# ACB-Light-R1_0-J04.net
KiCad netlist of a schematic drawn in EAGLE
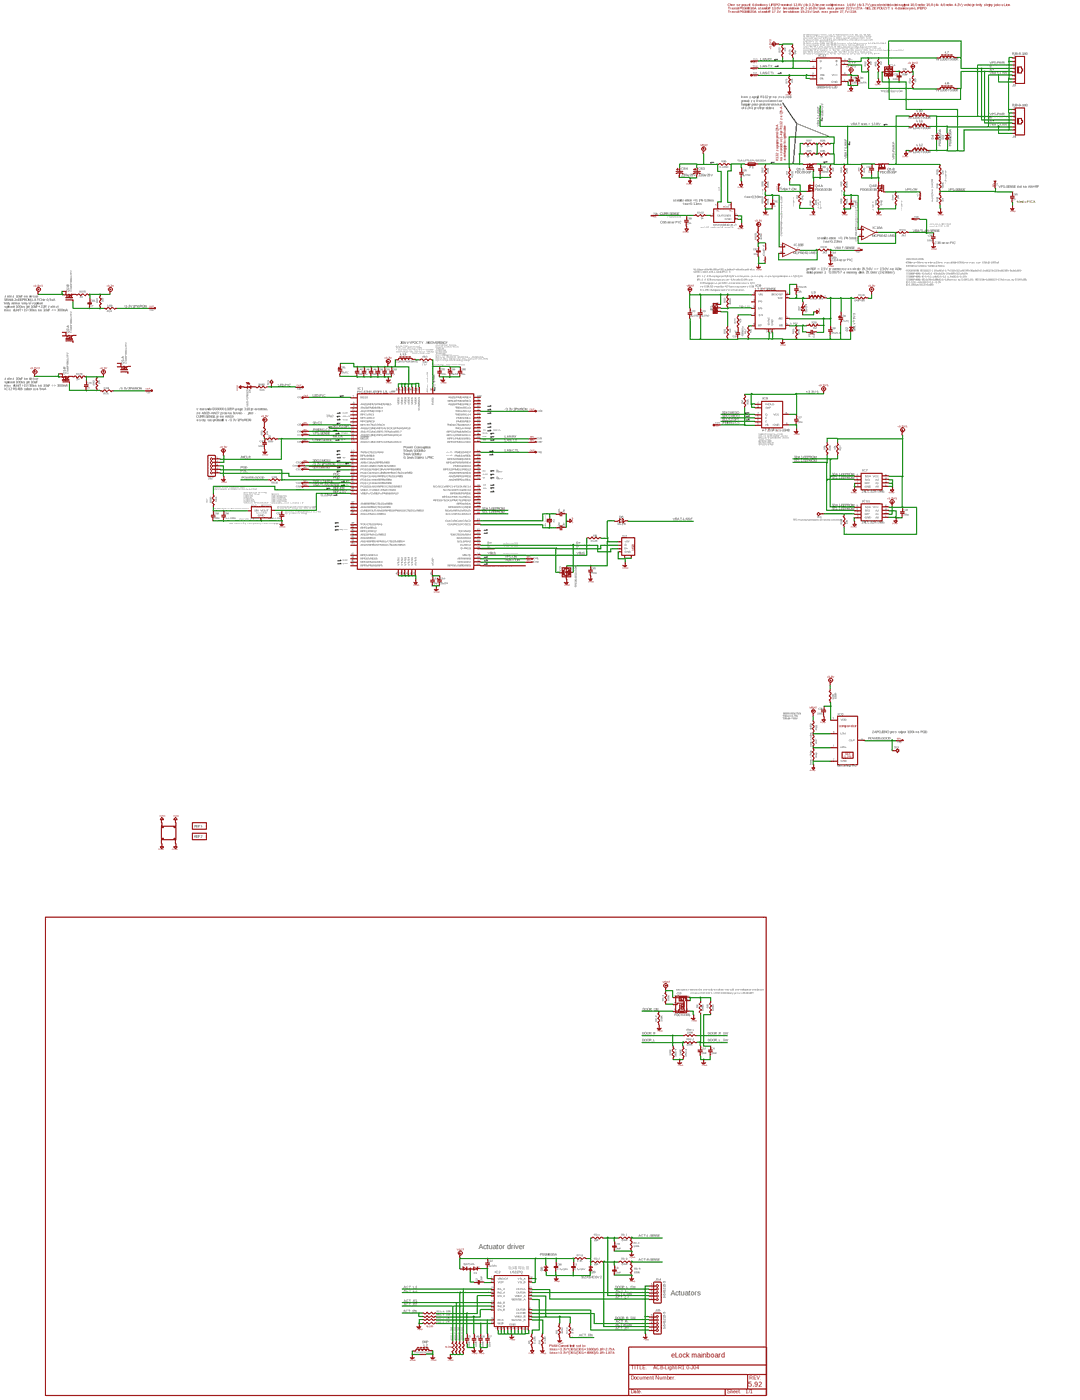
[diagram p0: schematic, sheet 1, overview]
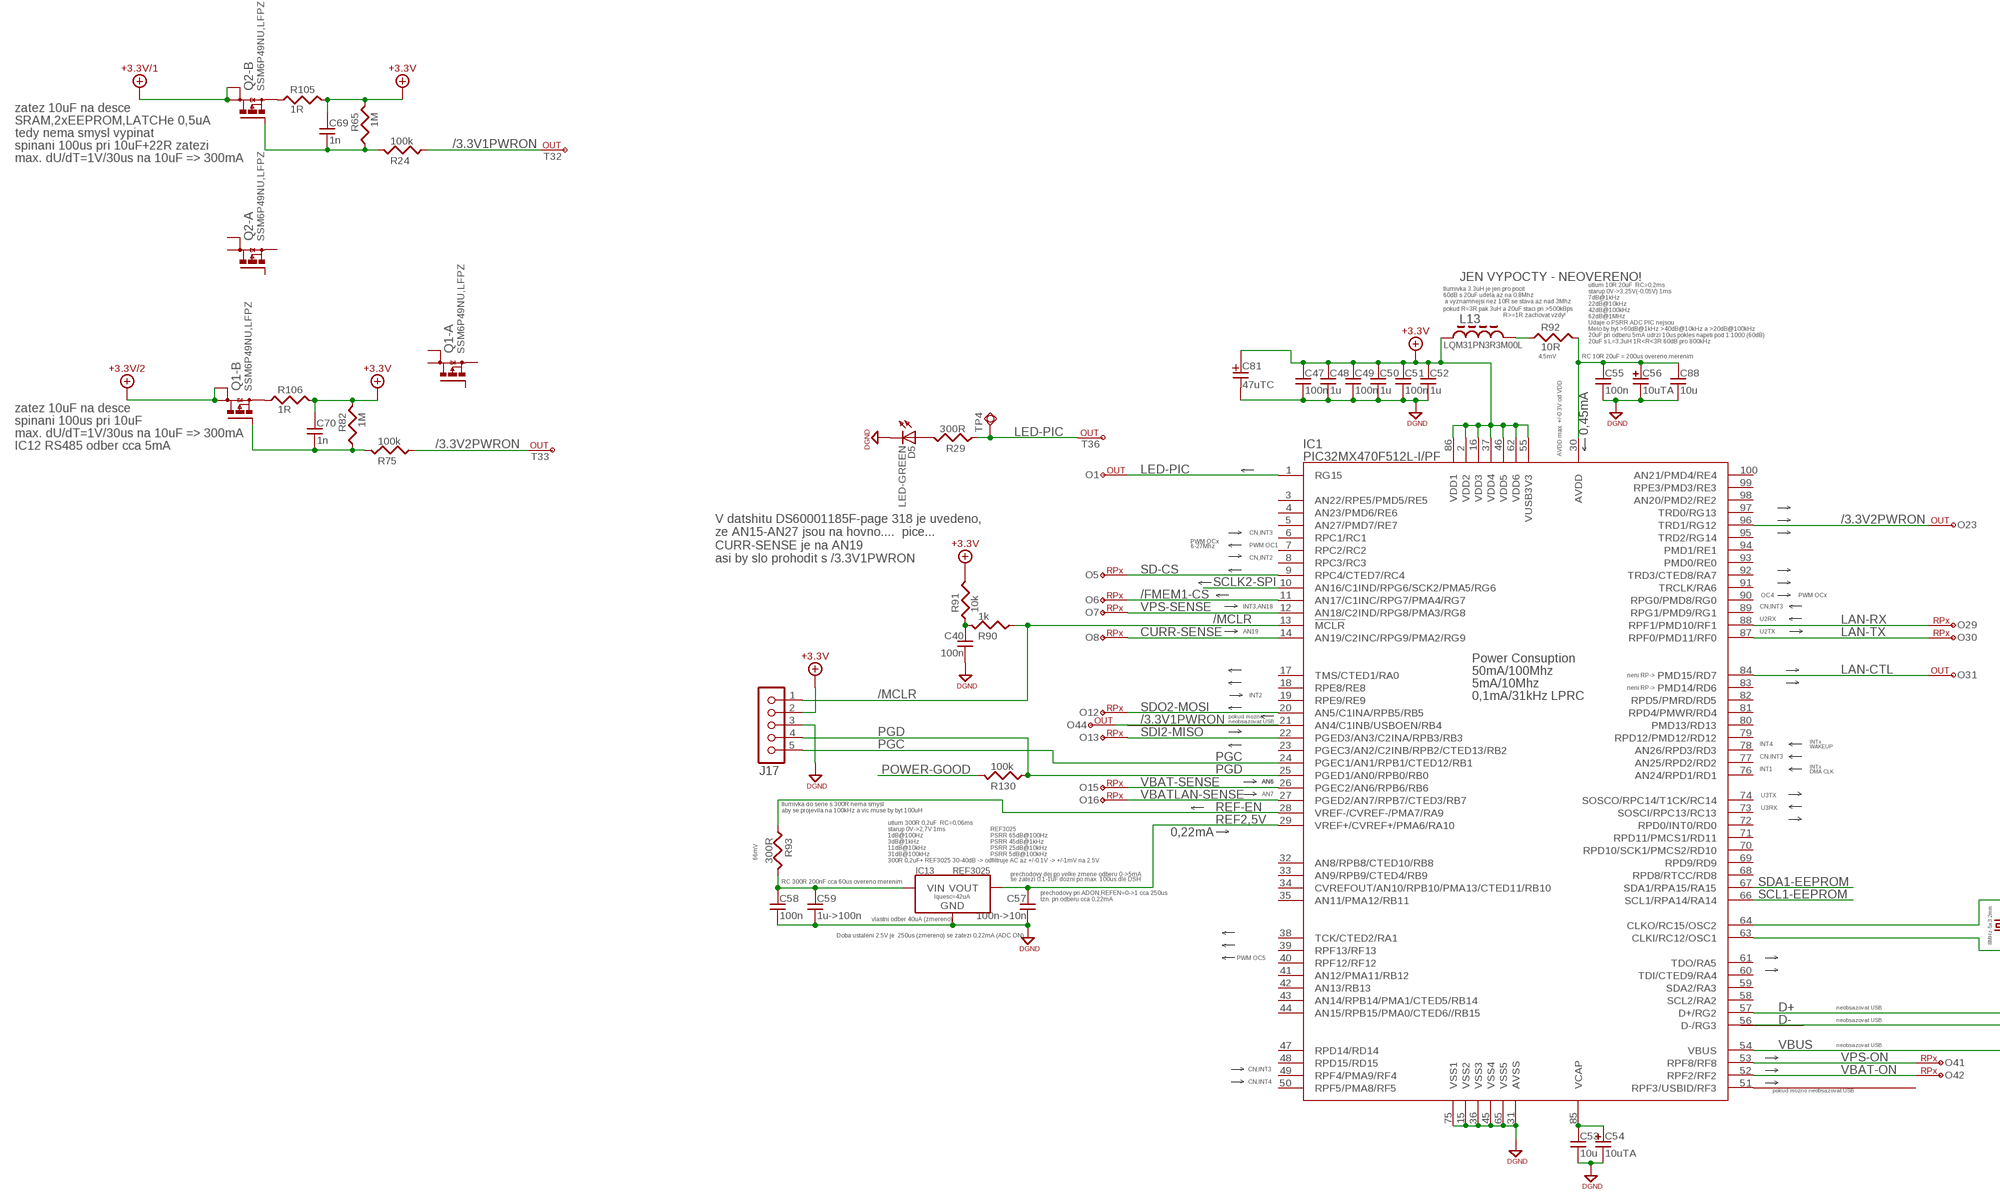
[diagram p1: schematic, sheet 1, part 1 of 5]
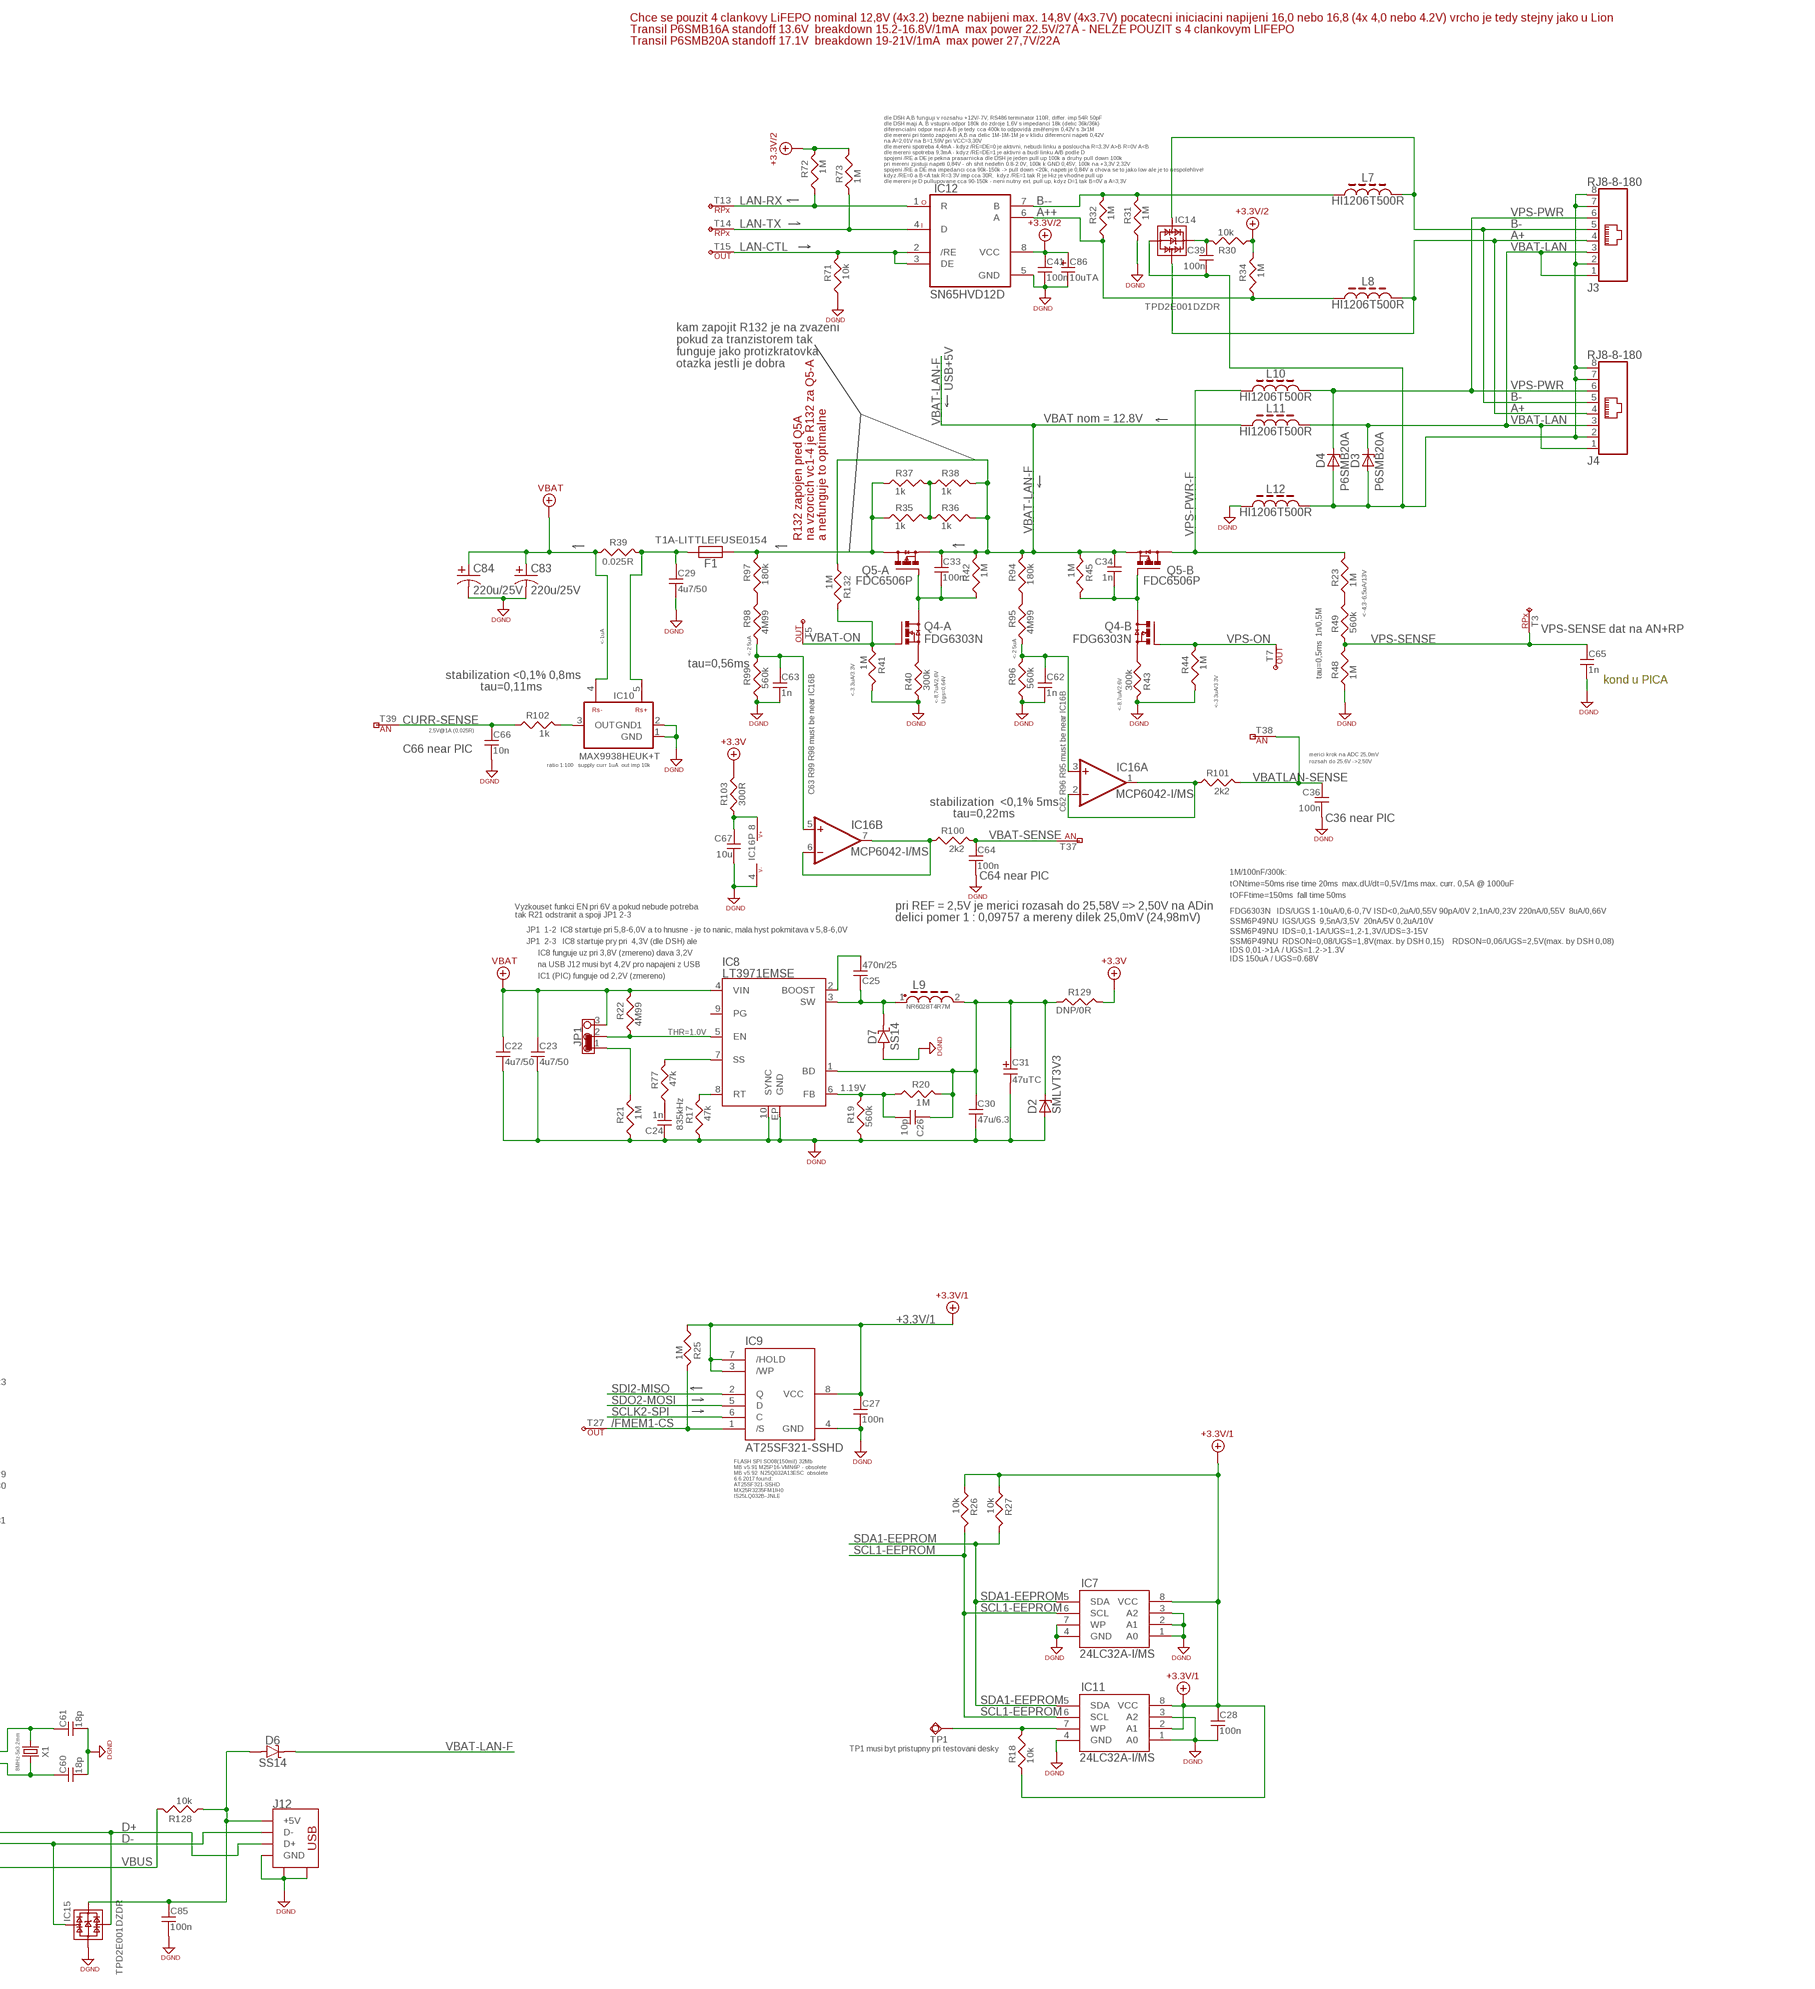
[diagram p2: schematic, sheet 1, part 2 of 5]
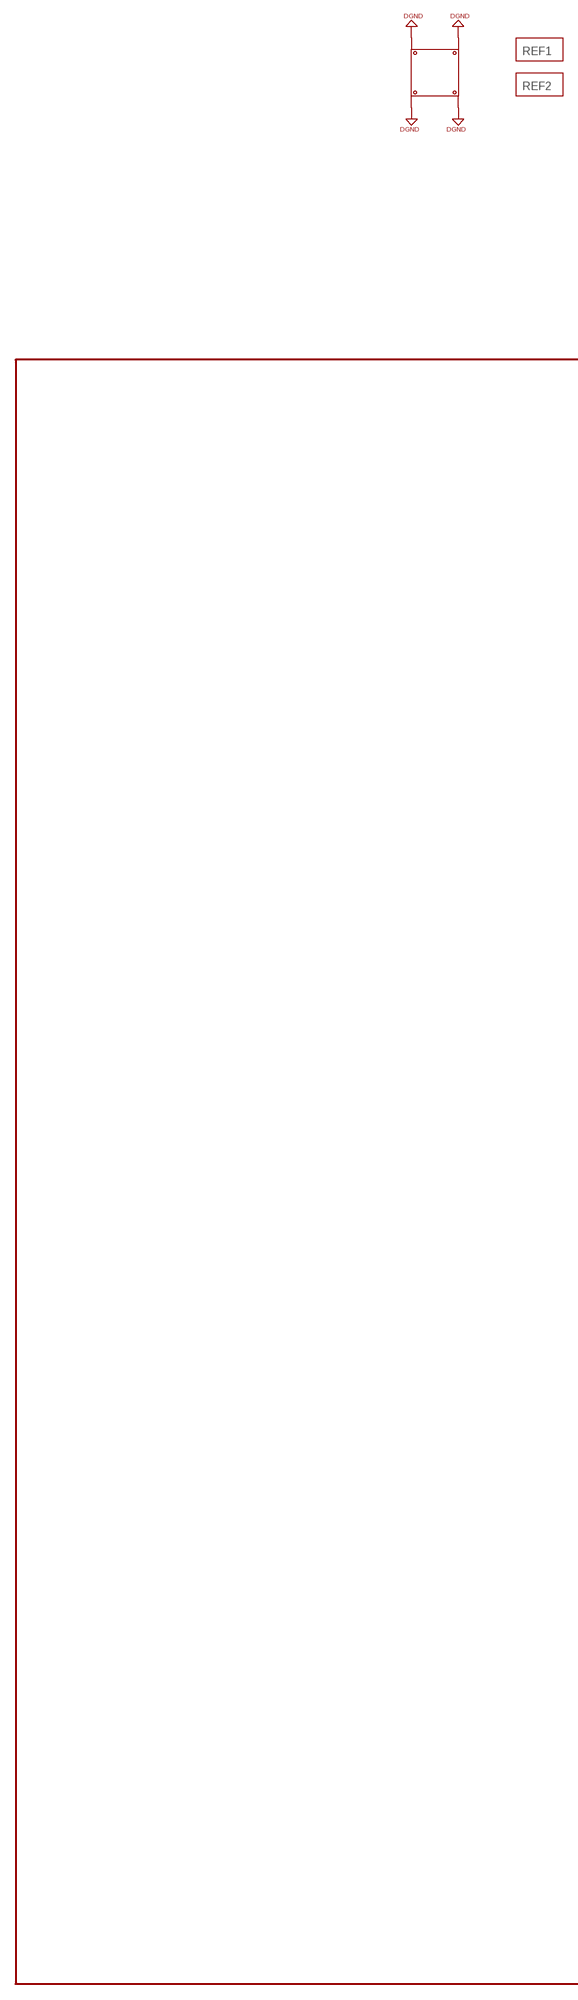
[diagram p3: schematic, sheet 1, part 3 of 5]
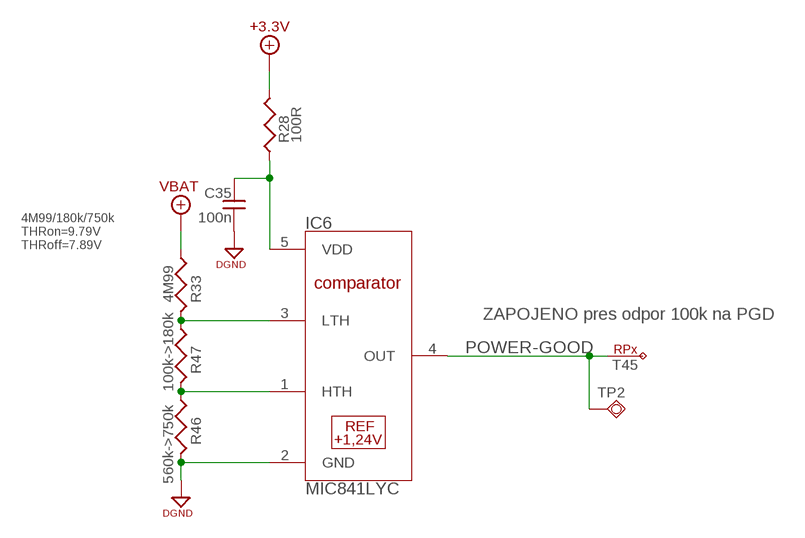
[diagram p4: schematic, sheet 1, part 4 of 5]
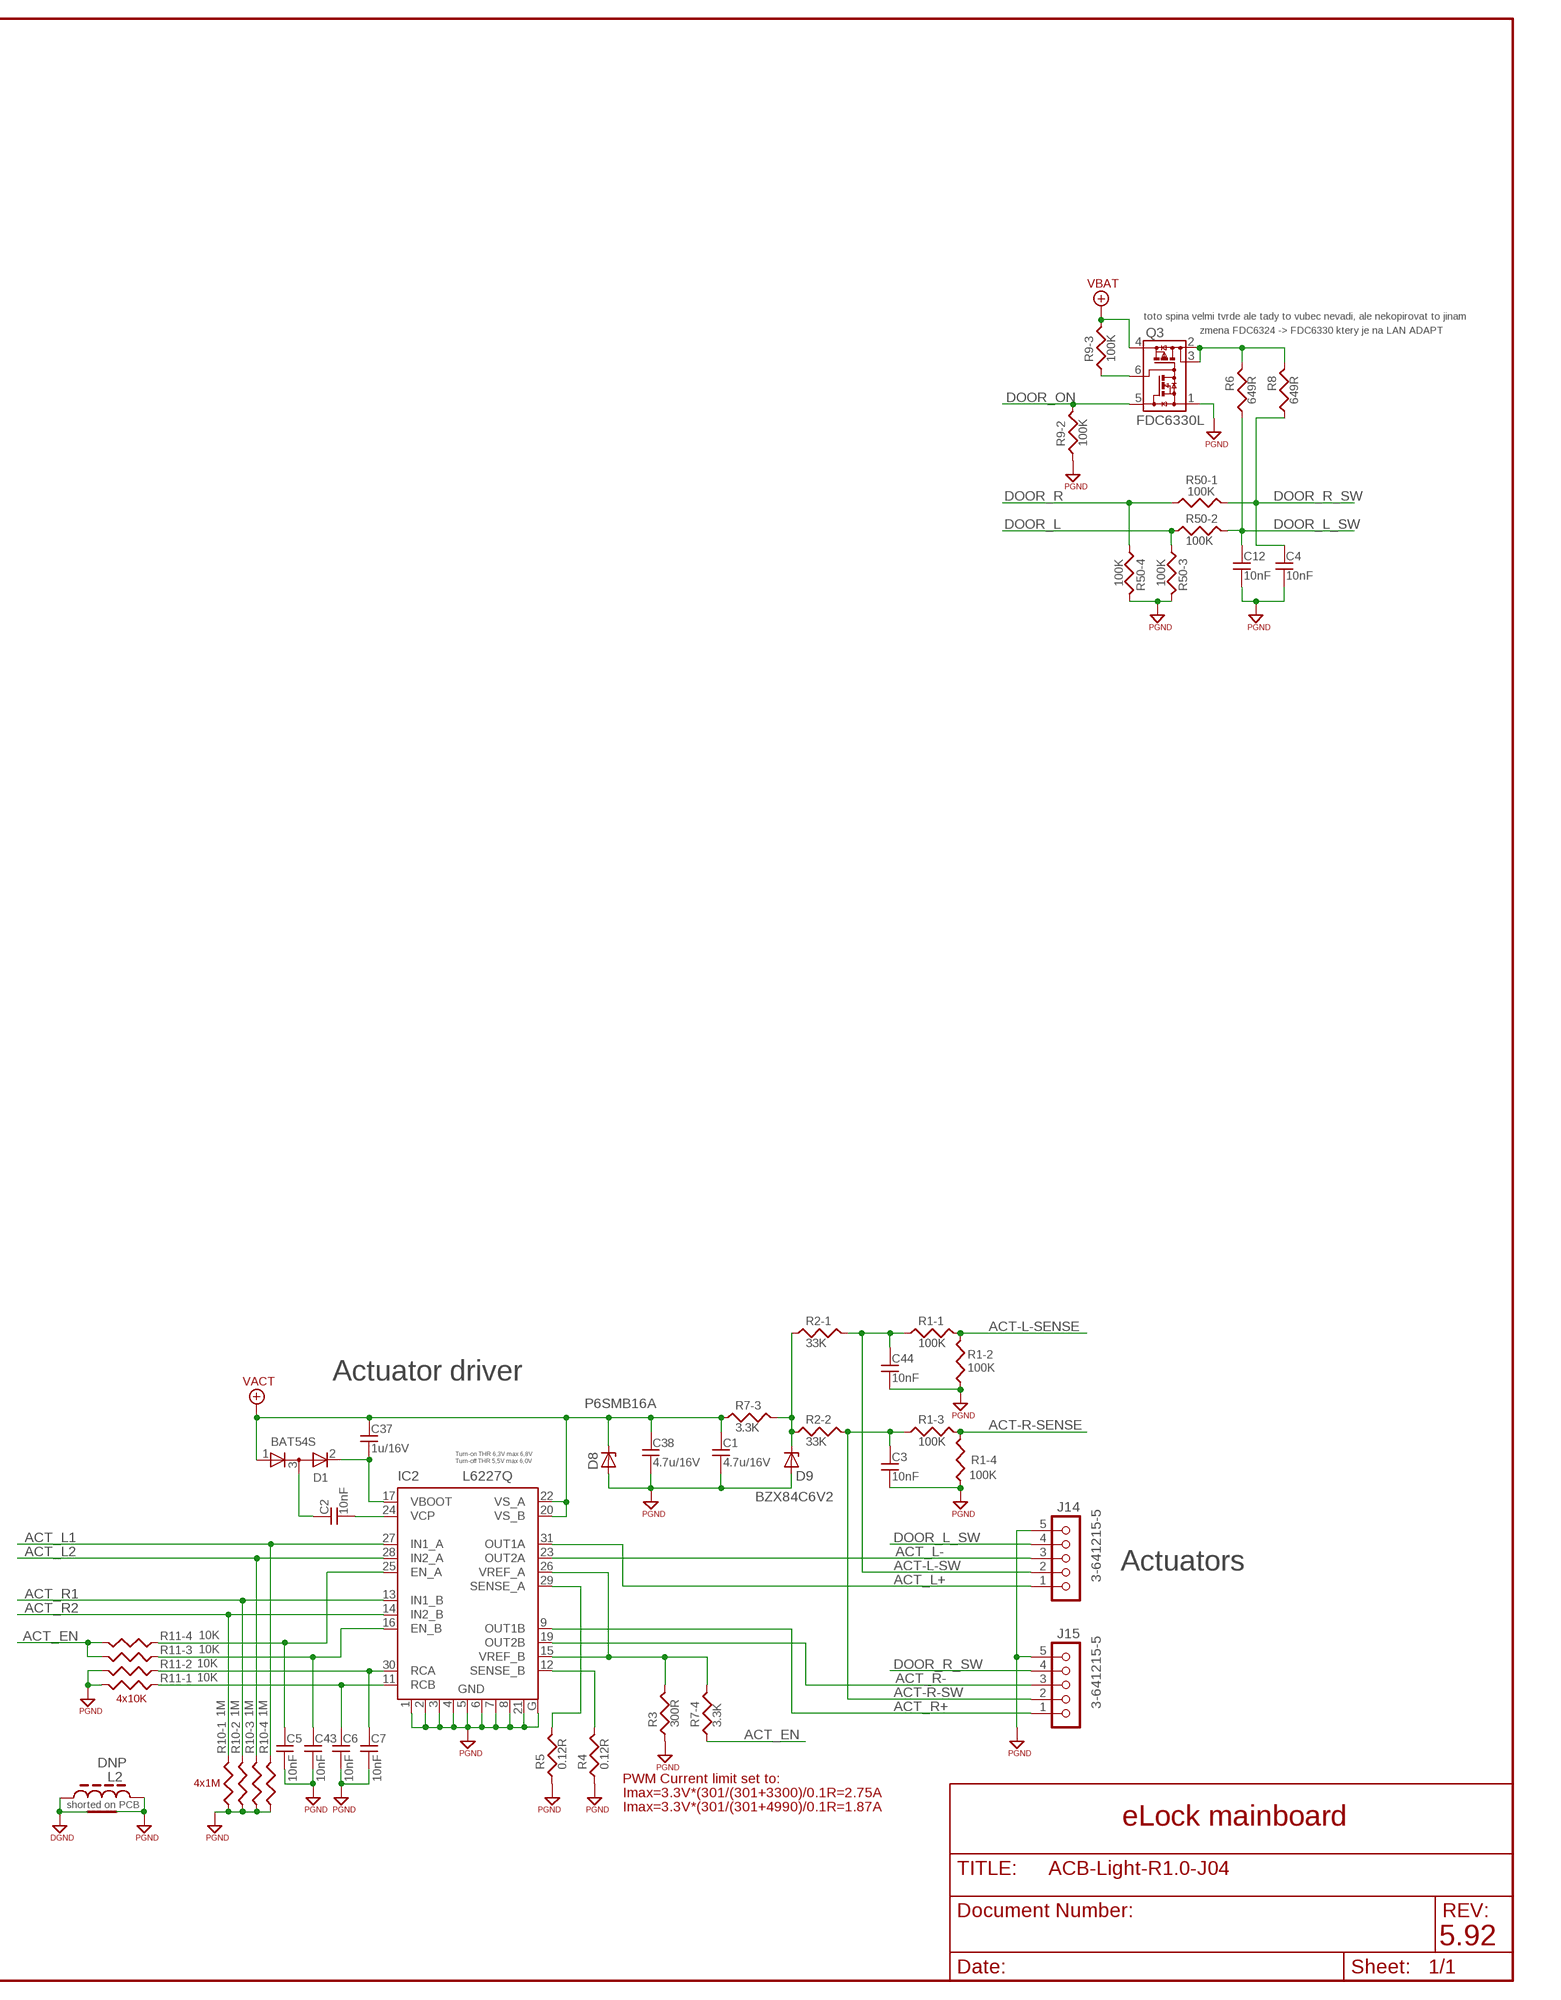
[diagram p5: schematic, sheet 1, part 5 of 5]

(export (version "E")
  (design (tool "Eeschema 10.0.6"))
  (components
    (comp (ref "C1")
      (value "4.7u/16V")
      (footprint "eagle-import:0805")
      (libsource (lib "eagle-import") (part "C-0805"))
    )
    (comp (ref "C2")
      (value "10nF")
      (footprint "eagle-import:0603")
      (libsource (lib "eagle-import") (part "C-0603"))
    )
    (comp (ref "C3")
      (value "10nF")
      (footprint "eagle-import:0603")
      (libsource (lib "eagle-import") (part "C-0603"))
    )
    (comp (ref "C4")
      (value "10nF")
      (footprint "eagle-import:0603")
      (libsource (lib "eagle-import") (part "C-0603"))
    )
    (comp (ref "C5")
      (value "10nF")
      (footprint "eagle-import:0603")
      (libsource (lib "eagle-import") (part "C-0603"))
    )
    (comp (ref "C6")
      (value "10nF")
      (footprint "eagle-import:0603")
      (libsource (lib "eagle-import") (part "C-0603"))
    )
    (comp (ref "C7")
      (value "10nF")
      (footprint "eagle-import:0603")
      (libsource (lib "eagle-import") (part "C-0603"))
    )
    (comp (ref "C12")
      (value "10nF")
      (footprint "eagle-import:0603")
      (libsource (lib "eagle-import") (part "C-0603"))
    )
    (comp (ref "C22")
      (value "4u7/50")
      (footprint "eagle-import:1206")
      (libsource (lib "eagle-import") (part "C-1206"))
    )
    (comp (ref "C23")
      (value "4u7/50")
      (footprint "eagle-import:1206")
      (libsource (lib "eagle-import") (part "C-1206"))
    )
    (comp (ref "C24")
      (value "1n")
      (footprint "eagle-import:0603")
      (libsource (lib "eagle-import") (part "C-0603"))
    )
    (comp (ref "C25")
      (value "470n/25")
      (footprint "eagle-import:0603")
      (libsource (lib "eagle-import") (part "C-0603"))
    )
    (comp (ref "C26")
      (value "10p")
      (footprint "eagle-import:0603")
      (libsource (lib "eagle-import") (part "C-0603"))
    )
    (comp (ref "C27")
      (value "100n")
      (footprint "eagle-import:0603")
      (libsource (lib "eagle-import") (part "C-0603"))
    )
    (comp (ref "C28")
      (value "100n")
      (footprint "eagle-import:0603")
      (libsource (lib "eagle-import") (part "C-0603"))
    )
    (comp (ref "C29")
      (value "4u7/50")
      (footprint "eagle-import:1206")
      (libsource (lib "eagle-import") (part "C-1206"))
    )
    (comp (ref "C30")
      (value "47u/6.3")
      (footprint "eagle-import:1206")
      (libsource (lib "eagle-import") (part "C-1206"))
    )
    (comp (ref "C31")
      (value "47uTC")
      (footprint "eagle-import:CT-C")
      (libsource (lib "eagle-import") (part "CT-C"))
    )
    (comp (ref "C33")
      (value "100n")
      (footprint "eagle-import:0603")
      (libsource (lib "eagle-import") (part "C-0603"))
    )
    (comp (ref "C34")
      (value "1n")
      (footprint "eagle-import:0603")
      (libsource (lib "eagle-import") (part "C-0603"))
    )
    (comp (ref "C35")
      (value "100n")
      (footprint "eagle-import:0603")
      (libsource (lib "eagle-import") (part "C-0603"))
    )
    (comp (ref "C36")
      (value "100n")
      (footprint "eagle-import:0603")
      (libsource (lib "eagle-import") (part "C-0603"))
    )
    (comp (ref "C37")
      (value "1u/16V")
      (footprint "eagle-import:0603")
      (libsource (lib "eagle-import") (part "C-0603"))
    )
    (comp (ref "C38")
      (value "4.7u/16V")
      (footprint "eagle-import:0805")
      (libsource (lib "eagle-import") (part "C-0805"))
    )
    (comp (ref "C39")
      (value "100n")
      (footprint "eagle-import:0603")
      (libsource (lib "eagle-import") (part "C-0603"))
    )
    (comp (ref "C40")
      (value "100n")
      (footprint "eagle-import:0603")
      (libsource (lib "eagle-import") (part "C-0603"))
    )
    (comp (ref "C41")
      (value "100n")
      (footprint "eagle-import:0603")
      (libsource (lib "eagle-import") (part "C-0603"))
    )
    (comp (ref "C43")
      (value "10nF")
      (footprint "eagle-import:0603")
      (libsource (lib "eagle-import") (part "C-0603"))
    )
    (comp (ref "C44")
      (value "10nF")
      (footprint "eagle-import:0603")
      (libsource (lib "eagle-import") (part "C-0603"))
    )
    (comp (ref "C47")
      (value "100n")
      (footprint "eagle-import:0603")
      (libsource (lib "eagle-import") (part "C-0603"))
    )
    (comp (ref "C48")
      (value "1u")
      (footprint "eagle-import:0603")
      (libsource (lib "eagle-import") (part "C-0603"))
    )
    (comp (ref "C49")
      (value "100n")
      (footprint "eagle-import:0603")
      (libsource (lib "eagle-import") (part "C-0603"))
    )
    (comp (ref "C50")
      (value "1u")
      (footprint "eagle-import:0603")
      (libsource (lib "eagle-import") (part "C-0603"))
    )
    (comp (ref "C51")
      (value "100n")
      (footprint "eagle-import:0603")
      (libsource (lib "eagle-import") (part "C-0603"))
    )
    (comp (ref "C52")
      (value "1u")
      (footprint "eagle-import:0603")
      (libsource (lib "eagle-import") (part "C-0603"))
    )
    (comp (ref "C53")
      (value "10u")
      (footprint "eagle-import:0603")
      (libsource (lib "eagle-import") (part "C-0603"))
    )
    (comp (ref "C54")
      (value "10uTA")
      (footprint "eagle-import:1206-POL-C")
      (libsource (lib "eagle-import") (part "CT-1206"))
    )
    (comp (ref "C55")
      (value "100n")
      (footprint "eagle-import:0603")
      (libsource (lib "eagle-import") (part "C-0603"))
    )
    (comp (ref "C56")
      (value "10uTA")
      (footprint "eagle-import:1206-POL-C")
      (libsource (lib "eagle-import") (part "CT-1206"))
    )
    (comp (ref "C57")
      (value "100n->10n")
      (footprint "eagle-import:0603")
      (libsource (lib "eagle-import") (part "C-0603"))
    )
    (comp (ref "C58")
      (value "100n")
      (footprint "eagle-import:0603")
      (libsource (lib "eagle-import") (part "C-0603"))
    )
    (comp (ref "C59")
      (value "1u->100n")
      (footprint "eagle-import:0603")
      (libsource (lib "eagle-import") (part "C-0603"))
    )
    (comp (ref "C60")
      (value "18p")
      (footprint "eagle-import:0603")
      (libsource (lib "eagle-import") (part "C-0603"))
    )
    (comp (ref "C61")
      (value "18p")
      (footprint "eagle-import:0603")
      (libsource (lib "eagle-import") (part "C-0603"))
    )
    (comp (ref "C62")
      (value "1n")
      (footprint "eagle-import:0603")
      (libsource (lib "eagle-import") (part "C-0603"))
    )
    (comp (ref "C63")
      (value "1n")
      (footprint "eagle-import:0603")
      (libsource (lib "eagle-import") (part "C-0603"))
    )
    (comp (ref "C64")
      (value "100n")
      (footprint "eagle-import:0603")
      (libsource (lib "eagle-import") (part "C-0603"))
    )
    (comp (ref "C65")
      (value "1n")
      (footprint "eagle-import:0603")
      (libsource (lib "eagle-import") (part "C-0603"))
    )
    (comp (ref "C66")
      (value "10n")
      (footprint "eagle-import:0603")
      (libsource (lib "eagle-import") (part "C-0603"))
    )
    (comp (ref "C67")
      (value "10u")
      (footprint "eagle-import:0603")
      (libsource (lib "eagle-import") (part "C-0603"))
    )
    (comp (ref "C69")
      (value "1n")
      (footprint "eagle-import:0603")
      (libsource (lib "eagle-import") (part "C-0603"))
    )
    (comp (ref "C70")
      (value "1n")
      (footprint "eagle-import:0603")
      (libsource (lib "eagle-import") (part "C-0603"))
    )
    (comp (ref "C81")
      (value "47uTC")
      (footprint "eagle-import:CT-C")
      (libsource (lib "eagle-import") (part "CT-C"))
    )
    (comp (ref "C83")
      (value "220u/25V")
      (footprint "eagle-import:CAP_8MM_DIA_SMT")
      (libsource (lib "eagle-import") (part "CAP-ELEC-SMD-8MM"))
    )
    (comp (ref "C84")
      (value "220u/25V")
      (footprint "eagle-import:CAP_8MM_DIA_SMT")
      (libsource (lib "eagle-import") (part "CAP-ELEC-SMD-8MM"))
    )
    (comp (ref "C85")
      (value "100n")
      (footprint "eagle-import:0603")
      (libsource (lib "eagle-import") (part "C-0603"))
    )
    (comp (ref "C86")
      (value "10uTA")
      (footprint "eagle-import:1206-POL-C")
      (libsource (lib "eagle-import") (part "CT-1206"))
    )
    (comp (ref "C88")
      (value "10u")
      (footprint "eagle-import:0603")
      (libsource (lib "eagle-import") (part "C-0603"))
    )
    (comp (ref "D1")
      (value "BAT54S")
      (footprint "eagle-import:SOT-23")
      (libsource (lib "eagle-import") (part "BAT54S"))
    )
    (comp (ref "D2")
      (value "SMLVT3V3")
      (footprint "eagle-import:SMA")
      (libsource (lib "eagle-import") (part "SMLVT3V3"))
    )
    (comp (ref "D3")
      (value "P6SMB20A")
      (footprint "eagle-import:SMB")
      (libsource (lib "eagle-import") (part "P6SMB"))
    )
    (comp (ref "D4")
      (value "P6SMB20A")
      (footprint "eagle-import:SMB")
      (libsource (lib "eagle-import") (part "P6SMB"))
    )
    (comp (ref "D5")
      (value "LED-GREEN")
      (footprint "eagle-import:0805-POL-D")
      (libsource (lib "eagle-import") (part "LED-0805"))
    )
    (comp (ref "D6")
      (value "SS14")
      (footprint "eagle-import:SMA")
      (libsource (lib "eagle-import") (part "DS-SMA"))
    )
    (comp (ref "D7")
      (value "SS14")
      (footprint "eagle-import:SMA")
      (libsource (lib "eagle-import") (part "DS-SMA"))
    )
    (comp (ref "D8")
      (value "P6SMB16A")
      (footprint "eagle-import:SMB")
      (libsource (lib "eagle-import") (part "P6SMB"))
    )
    (comp (ref "D9")
      (value "BZX84C6V2")
      (footprint "eagle-import:SOT-23")
      (libsource (lib "eagle-import") (part "BZX84C6V2"))
    )
    (comp (ref "F1")
      (value "T1A-LITTLEFUSE0154")
      (footprint "eagle-import:LITTLEFUSE0154")
      (libsource (lib "eagle-import") (part "POJISTKA-LITTLEFUSE0154"))
    )
    (comp (ref "IC1")
      (value "PIC32MX470F512L-I/PF")
      (footprint "eagle-import:TQFP100_14X14_0,5MM")
      (libsource (lib "eagle-import") (part "PIC32MX470F512L-I/PF"))
    )
    (comp (ref "IC2")
      (value "L6227Q")
      (footprint "eagle-import:SQFP-S-5X5-32")
      (libsource (lib "eagle-import") (part "L6227Q"))
    )
    (comp (ref "IC6")
      (value "MIC841LYC")
      (footprint "eagle-import:SC-70-5")
      (libsource (lib "eagle-import") (part "MIC841LYC"))
    )
    (comp (ref "IC7")
      (value "24LC32A-I/MS")
      (footprint "eagle-import:MSOP-08")
      (libsource (lib "eagle-import") (part "24-I/MS"))
    )
    (comp (ref "IC8")
      (value "LT3971EMSE")
      (footprint "eagle-import:MSOP10EXP")
      (libsource (lib "eagle-import") (part "LT3971EMSE"))
    )
    (comp (ref "IC9")
      (value "AT25SF321-SSHD")
      (footprint "eagle-import:SO-08")
      (libsource (lib "eagle-import") (part "M25P16-VMN6P"))
    )
    (comp (ref "IC10")
      (value "MAX9938HEUK+T")
      (footprint "eagle-import:SOT23-5")
      (libsource (lib "eagle-import") (part "TSM9938HEUK+T"))
    )
    (comp (ref "IC11")
      (value "24LC32A-I/MS")
      (footprint "eagle-import:MSOP-08")
      (libsource (lib "eagle-import") (part "24-I/MS"))
    )
    (comp (ref "IC12")
      (value "SN65HVD12D")
      (footprint "eagle-import:SO08")
      (libsource (lib "eagle-import") (part "SN65HVD3082ED"))
    )
    (comp (ref "IC13")
      (value "REF3025")
      (footprint "eagle-import:SOT23")
      (libsource (lib "eagle-import") (part "REF3025"))
    )
    (comp (ref "IC14")
      (value "TPD2E001DZDR")
      (footprint "eagle-import:SOT-143")
      (libsource (lib "eagle-import") (part "SR05.TCT"))
    )
    (comp (ref "IC15")
      (value "TPD2E001DZDR")
      (footprint "eagle-import:SOT-143")
      (libsource (lib "eagle-import") (part "SR05.TCT"))
    )
    (comp (ref "IC16")
      (value "MCP6042-I/MS")
      (footprint "eagle-import:MSOP-08")
      (libsource (lib "eagle-import") (part "MCP6042-I/MS"))
    )
    (comp (ref "J3")
      (value "RJ8-8-180")
      (footprint "eagle-import:RJ8-8-180")
      (libsource (lib "eagle-import") (part "RJ8-8-180"))
    )
    (comp (ref "J4")
      (value "RJ8-8-180")
      (footprint "eagle-import:RJ8-8-180")
      (libsource (lib "eagle-import") (part "RJ8-8-180"))
    )
    (comp (ref "J12")
      (value "USB_A_180")
      (footprint "eagle-import:USB_B_180")
      (libsource (lib "eagle-import") (part "USB_B_180"))
    )
    (comp (ref "J14")
      (value "3-641215-5")
      (footprint "eagle-import:3-641215-5")
      (libsource (lib "eagle-import") (part "3-641215-5"))
    )
    (comp (ref "J15")
      (value "3-641215-5")
      (footprint "eagle-import:3-641215-5")
      (libsource (lib "eagle-import") (part "3-641215-5"))
    )
    (comp (ref "J17")
      (value "DNP-open-hole")
      (footprint "eagle-import:MA05-1")
      (libsource (lib "eagle-import") (part "MA05-1"))
    )
    (comp (ref "JP1")
      (value "JP3CLOSE12")
      (footprint "eagle-import:JP3CLOSE12")
      (libsource (lib "eagle-import") (part "JP3CLOSE12"))
    )
    (comp (ref "L2")
      (value "DNP")
      (footprint "eagle-import:0805-0RTOP")
      (libsource (lib "eagle-import") (part "L-0805-0R"))
    )
    (comp (ref "L7")
      (value "HI1206T500R")
      (footprint "eagle-import:1206")
      (libsource (lib "eagle-import") (part "L-1206"))
    )
    (comp (ref "L8")
      (value "HI1206T500R")
      (footprint "eagle-import:1206")
      (libsource (lib "eagle-import") (part "L-1206"))
    )
    (comp (ref "L9")
      (value "NR6028T4R7M")
      (footprint "eagle-import:NR6028")
      (libsource (lib "eagle-import") (part "NR6028"))
    )
    (comp (ref "L10")
      (value "HI1206T500R")
      (footprint "eagle-import:1206")
      (libsource (lib "eagle-import") (part "L-1206"))
    )
    (comp (ref "L11")
      (value "HI1206T500R")
      (footprint "eagle-import:1206")
      (libsource (lib "eagle-import") (part "L-1206"))
    )
    (comp (ref "L12")
      (value "HI1206T500R")
      (footprint "eagle-import:1206")
      (libsource (lib "eagle-import") (part "L-1206"))
    )
    (comp (ref "L13")
      (value "LQM31PN3R3M00L")
      (footprint "eagle-import:1206")
      (libsource (lib "eagle-import") (part "L-1206"))
    )
    (comp (ref "O1")
      (value "PIC-OUT")
      (footprint "eagle-import:TEMP-PAD")
      (libsource (lib "eagle-import") (part "PIC-OUT"))
    )
    (comp (ref "O5")
      (value "PIC-RPX")
      (footprint "eagle-import:TEMP-PAD")
      (libsource (lib "eagle-import") (part "PIC-RPX"))
    )
    (comp (ref "O6")
      (value "PIC-RPX")
      (footprint "eagle-import:TEMP-PAD")
      (libsource (lib "eagle-import") (part "PIC-RPX"))
    )
    (comp (ref "O7")
      (value "PIC-RPX")
      (footprint "eagle-import:TEMP-PAD")
      (libsource (lib "eagle-import") (part "PIC-RPX"))
    )
    (comp (ref "O8")
      (value "PIC-RPX")
      (footprint "eagle-import:TEMP-PAD")
      (libsource (lib "eagle-import") (part "PIC-RPX"))
    )
    (comp (ref "O12")
      (value "PIC-RPX")
      (footprint "eagle-import:TEMP-PAD")
      (libsource (lib "eagle-import") (part "PIC-RPX"))
    )
    (comp (ref "O13")
      (value "PIC-RPX")
      (footprint "eagle-import:TEMP-PAD")
      (libsource (lib "eagle-import") (part "PIC-RPX"))
    )
    (comp (ref "O15")
      (value "PIC-RPX")
      (footprint "eagle-import:TEMP-PAD")
      (libsource (lib "eagle-import") (part "PIC-RPX"))
    )
    (comp (ref "O16")
      (value "PIC-RPX")
      (footprint "eagle-import:TEMP-PAD")
      (libsource (lib "eagle-import") (part "PIC-RPX"))
    )
    (comp (ref "O23")
      (value "PIC-OUT")
      (footprint "eagle-import:TEMP-PAD")
      (libsource (lib "eagle-import") (part "PIC-OUT"))
    )
    (comp (ref "O29")
      (value "PIC-RPX")
      (footprint "eagle-import:TEMP-PAD")
      (libsource (lib "eagle-import") (part "PIC-RPX"))
    )
    (comp (ref "O30")
      (value "PIC-RPX")
      (footprint "eagle-import:TEMP-PAD")
      (libsource (lib "eagle-import") (part "PIC-RPX"))
    )
    (comp (ref "O31")
      (value "PIC-OUT")
      (footprint "eagle-import:TEMP-PAD")
      (libsource (lib "eagle-import") (part "PIC-OUT"))
    )
    (comp (ref "O41")
      (value "PIC-RPX")
      (footprint "eagle-import:TEMP-PAD")
      (libsource (lib "eagle-import") (part "PIC-RPX"))
    )
    (comp (ref "O42")
      (value "PIC-RPX")
      (footprint "eagle-import:TEMP-PAD")
      (libsource (lib "eagle-import") (part "PIC-RPX"))
    )
    (comp (ref "O44")
      (value "PIC-OUT")
      (footprint "eagle-import:TEMP-PAD")
      (libsource (lib "eagle-import") (part "PIC-OUT"))
    )
    (comp (ref "PCB1")
      (value "PCB-ACB")
      (footprint "eagle-import:PCB-ACB")
      (libsource (lib "eagle-import") (part "PCB-ACB-1"))
    )
    (comp (ref "Q1")
      (value "SSM6P49NU,LFPZ")
      (footprint "eagle-import:MICRO_FET")
      (libsource (lib "eagle-import") (part "SSM6P49PZNU,LF"))
    )
    (comp (ref "Q2")
      (value "SSM6P49NU,LFPZ")
      (footprint "eagle-import:MICRO_FET")
      (libsource (lib "eagle-import") (part "SSM6P49PZNU,LF"))
    )
    (comp (ref "Q3")
      (value "FDC6330L")
      (footprint "eagle-import:SSOT-6")
      (libsource (lib "eagle-import") (part "FDC6330L"))
    )
    (comp (ref "Q4")
      (value "FDG6303N")
      (footprint "eagle-import:SC70-6")
      (libsource (lib "eagle-import") (part "FDG6303N"))
    )
    (comp (ref "Q5")
      (value "FDC6506P")
      (footprint "eagle-import:SSOT-6")
      (libsource (lib "eagle-import") (part "FDC6506D"))
    )
    (comp (ref "R1")
      (value "100K")
      (footprint "eagle-import:0603-ARRAY")
      (libsource (lib "eagle-import") (part "EXB-38"))
    )
    (comp (ref "R2")
      (value "33K")
      (footprint "eagle-import:0603-ARRAY")
      (libsource (lib "eagle-import") (part "EXB-38"))
    )
    (comp (ref "R3")
      (value "300R")
      (footprint "eagle-import:0603")
      (libsource (lib "eagle-import") (part "R-0603"))
    )
    (comp (ref "R4")
      (value "0.12R")
      (footprint "eagle-import:0805")
      (libsource (lib "eagle-import") (part "R-0805"))
    )
    (comp (ref "R5")
      (value "0.12R")
      (footprint "eagle-import:0805")
      (libsource (lib "eagle-import") (part "R-0805"))
    )
    (comp (ref "R6")
      (value "649R")
      (footprint "eagle-import:0603")
      (libsource (lib "eagle-import") (part "R-0603"))
    )
    (comp (ref "R7")
      (value "3.3K")
      (footprint "eagle-import:0603-ARRAY")
      (libsource (lib "eagle-import") (part "EXB-38"))
    )
    (comp (ref "R8")
      (value "649R")
      (footprint "eagle-import:0603")
      (libsource (lib "eagle-import") (part "R-0603"))
    )
    (comp (ref "R9")
      (value "100K")
      (footprint "eagle-import:0603-ARRAY")
      (libsource (lib "eagle-import") (part "EXB-38"))
    )
    (comp (ref "R10")
      (value "1M")
      (footprint "eagle-import:0603-ARRAY")
      (libsource (lib "eagle-import") (part "EXB-38"))
    )
    (comp (ref "R11")
      (value "10K")
      (footprint "eagle-import:0603-ARRAY")
      (libsource (lib "eagle-import") (part "EXB-38"))
    )
    (comp (ref "R17")
      (value "47k")
      (footprint "eagle-import:0603")
      (libsource (lib "eagle-import") (part "R-0603"))
    )
    (comp (ref "R18")
      (value "10k")
      (footprint "eagle-import:0603")
      (libsource (lib "eagle-import") (part "R-0603"))
    )
    (comp (ref "R19")
      (value "560k")
      (footprint "eagle-import:0603")
      (libsource (lib "eagle-import") (part "R-0603"))
    )
    (comp (ref "R20")
      (value "1M")
      (footprint "eagle-import:0603")
      (libsource (lib "eagle-import") (part "R-0603"))
    )
    (comp (ref "R21")
      (value "1M")
      (footprint "eagle-import:0603")
      (libsource (lib "eagle-import") (part "R-0603"))
    )
    (comp (ref "R22")
      (value "4M99")
      (footprint "eagle-import:0603")
      (libsource (lib "eagle-import") (part "R-0603"))
    )
    (comp (ref "R23")
      (value "1M")
      (footprint "eagle-import:0603")
      (libsource (lib "eagle-import") (part "R-0603"))
    )
    (comp (ref "R24")
      (value "100k")
      (footprint "eagle-import:0603")
      (libsource (lib "eagle-import") (part "R-0603"))
    )
    (comp (ref "R25")
      (value "1M")
      (footprint "eagle-import:0603")
      (libsource (lib "eagle-import") (part "R-0603"))
    )
    (comp (ref "R26")
      (value "10k")
      (footprint "eagle-import:0603")
      (libsource (lib "eagle-import") (part "R-0603"))
    )
    (comp (ref "R27")
      (value "10k")
      (footprint "eagle-import:0603")
      (libsource (lib "eagle-import") (part "R-0603"))
    )
    (comp (ref "R28")
      (value "100R")
      (footprint "eagle-import:0603")
      (libsource (lib "eagle-import") (part "R-0603"))
    )
    (comp (ref "R29")
      (value "300R")
      (footprint "eagle-import:0603")
      (libsource (lib "eagle-import") (part "R-0603"))
    )
    (comp (ref "R30")
      (value "10k")
      (footprint "eagle-import:0603")
      (libsource (lib "eagle-import") (part "R-0603"))
    )
    (comp (ref "R31")
      (value "1M")
      (footprint "eagle-import:0603")
      (libsource (lib "eagle-import") (part "R-0603"))
    )
    (comp (ref "R32")
      (value "1M")
      (footprint "eagle-import:0603")
      (libsource (lib "eagle-import") (part "R-0603"))
    )
    (comp (ref "R33")
      (value "4M99")
      (footprint "eagle-import:0603")
      (libsource (lib "eagle-import") (part "R-0603"))
    )
    (comp (ref "R34")
      (value "1M")
      (footprint "eagle-import:0603")
      (libsource (lib "eagle-import") (part "R-0603"))
    )
    (comp (ref "R35")
      (value "1k")
      (footprint "eagle-import:0805")
      (libsource (lib "eagle-import") (part "R-0805"))
    )
    (comp (ref "R36")
      (value "1k")
      (footprint "eagle-import:0805")
      (libsource (lib "eagle-import") (part "R-0805"))
    )
    (comp (ref "R37")
      (value "1k")
      (footprint "eagle-import:0805")
      (libsource (lib "eagle-import") (part "R-0805"))
    )
    (comp (ref "R38")
      (value "1k")
      (footprint "eagle-import:0805")
      (libsource (lib "eagle-import") (part "R-0805"))
    )
    (comp (ref "R39")
      (value "0.025R")
      (footprint "eagle-import:0805")
      (libsource (lib "eagle-import") (part "R-0805"))
    )
    (comp (ref "R40")
      (value "300k")
      (footprint "eagle-import:0603")
      (libsource (lib "eagle-import") (part "R-0603"))
    )
    (comp (ref "R41")
      (value "1M")
      (footprint "eagle-import:0603")
      (libsource (lib "eagle-import") (part "R-0603"))
    )
    (comp (ref "R42")
      (value "1M")
      (footprint "eagle-import:0603")
      (libsource (lib "eagle-import") (part "R-0603"))
    )
    (comp (ref "R43")
      (value "300k")
      (footprint "eagle-import:0603")
      (libsource (lib "eagle-import") (part "R-0603"))
    )
    (comp (ref "R44")
      (value "1M")
      (footprint "eagle-import:0603")
      (libsource (lib "eagle-import") (part "R-0603"))
    )
    (comp (ref "R45")
      (value "1M")
      (footprint "eagle-import:0603")
      (libsource (lib "eagle-import") (part "R-0603"))
    )
    (comp (ref "R46")
      (value "560k->750k")
      (footprint "eagle-import:0603")
      (libsource (lib "eagle-import") (part "R-0603"))
    )
    (comp (ref "R47")
      (value "100k->180k")
      (footprint "eagle-import:0603")
      (libsource (lib "eagle-import") (part "R-0603"))
    )
    (comp (ref "R48")
      (value "1M")
      (footprint "eagle-import:0603")
      (libsource (lib "eagle-import") (part "R-0603"))
    )
    (comp (ref "R49")
      (value "560k")
      (footprint "eagle-import:0603")
      (libsource (lib "eagle-import") (part "R-0603"))
    )
    (comp (ref "R50")
      (value "100K")
      (footprint "eagle-import:0603-ARRAY")
      (libsource (lib "eagle-import") (part "EXB-38"))
    )
    (comp (ref "R65")
      (value "1M")
      (footprint "eagle-import:0603")
      (libsource (lib "eagle-import") (part "R-0603"))
    )
    (comp (ref "R71")
      (value "10k")
      (footprint "eagle-import:0603")
      (libsource (lib "eagle-import") (part "R-0603"))
    )
    (comp (ref "R72")
      (value "1M")
      (footprint "eagle-import:0603")
      (libsource (lib "eagle-import") (part "R-0603"))
    )
    (comp (ref "R73")
      (value "1M")
      (footprint "eagle-import:0603")
      (libsource (lib "eagle-import") (part "R-0603"))
    )
    (comp (ref "R75")
      (value "100k")
      (footprint "eagle-import:0603")
      (libsource (lib "eagle-import") (part "R-0603"))
    )
    (comp (ref "R77")
      (value "47k")
      (footprint "eagle-import:0603")
      (libsource (lib "eagle-import") (part "R-0603"))
    )
    (comp (ref "R82")
      (value "1M")
      (footprint "eagle-import:0603")
      (libsource (lib "eagle-import") (part "R-0603"))
    )
    (comp (ref "R90")
      (value "1k")
      (footprint "eagle-import:0603")
      (libsource (lib "eagle-import") (part "R-0603"))
    )
    (comp (ref "R91")
      (value "10k")
      (footprint "eagle-import:0603")
      (libsource (lib "eagle-import") (part "R-0603"))
    )
    (comp (ref "R92")
      (value "10R")
      (footprint "eagle-import:0603")
      (libsource (lib "eagle-import") (part "R-0603"))
    )
    (comp (ref "R93")
      (value "300R")
      (footprint "eagle-import:0603")
      (libsource (lib "eagle-import") (part "R-0603"))
    )
    (comp (ref "R94")
      (value "180k")
      (footprint "eagle-import:0603")
      (libsource (lib "eagle-import") (part "R-0603"))
    )
    (comp (ref "R95")
      (value "4M99")
      (footprint "eagle-import:0603")
      (libsource (lib "eagle-import") (part "R-0603"))
    )
    (comp (ref "R96")
      (value "560k")
      (footprint "eagle-import:0603")
      (libsource (lib "eagle-import") (part "R-0603"))
    )
    (comp (ref "R97")
      (value "180k")
      (footprint "eagle-import:0603")
      (libsource (lib "eagle-import") (part "R-0603"))
    )
    (comp (ref "R98")
      (value "4M99")
      (footprint "eagle-import:0603")
      (libsource (lib "eagle-import") (part "R-0603"))
    )
    (comp (ref "R99")
      (value "560k")
      (footprint "eagle-import:0603")
      (libsource (lib "eagle-import") (part "R-0603"))
    )
    (comp (ref "R100")
      (value "2k2")
      (footprint "eagle-import:0603")
      (libsource (lib "eagle-import") (part "R-0603"))
    )
    (comp (ref "R101")
      (value "2k2")
      (footprint "eagle-import:0603")
      (libsource (lib "eagle-import") (part "R-0603"))
    )
    (comp (ref "R102")
      (value "1k")
      (footprint "eagle-import:0603")
      (libsource (lib "eagle-import") (part "R-0603"))
    )
    (comp (ref "R103")
      (value "300R")
      (footprint "eagle-import:0603")
      (libsource (lib "eagle-import") (part "R-0603"))
    )
    (comp (ref "R105")
      (value "1R")
      (footprint "eagle-import:0805")
      (libsource (lib "eagle-import") (part "R-0805"))
    )
    (comp (ref "R106")
      (value "1R")
      (footprint "eagle-import:0805")
      (libsource (lib "eagle-import") (part "R-0805"))
    )
    (comp (ref "R128")
      (value "10k")
      (footprint "eagle-import:0603")
      (libsource (lib "eagle-import") (part "R-0603"))
    )
    (comp (ref "R129")
      (value "DNP/0R")
      (footprint "eagle-import:0603")
      (libsource (lib "eagle-import") (part "R-0603"))
    )
    (comp (ref "R130")
      (value "100k")
      (footprint "eagle-import:0603")
      (libsource (lib "eagle-import") (part "R-0603"))
    )
    (comp (ref "R132")
      (value "1M")
      (footprint "eagle-import:0603")
      (libsource (lib "eagle-import") (part "R-0603"))
    )
    (comp (ref "REF1")
      (value "REF")
      (footprint "eagle-import:REF")
      (libsource (lib "eagle-import") (part "REF"))
    )
    (comp (ref "REF2")
      (value "REF")
      (footprint "eagle-import:REF")
      (libsource (lib "eagle-import") (part "REF"))
    )
    (comp (ref "T3")
      (value "PIC-RPX")
      (footprint "eagle-import:TEMP-PAD")
      (libsource (lib "eagle-import") (part "PIC-RPX"))
    )
    (comp (ref "T5")
      (value "PIC-OUT")
      (footprint "eagle-import:TEMP-PAD")
      (libsource (lib "eagle-import") (part "PIC-OUT"))
    )
    (comp (ref "T7")
      (value "PIC-OUT")
      (footprint "eagle-import:TEMP-PAD")
      (libsource (lib "eagle-import") (part "PIC-OUT"))
    )
    (comp (ref "T13")
      (value "PIC-RPX")
      (footprint "eagle-import:TEMP-PAD")
      (libsource (lib "eagle-import") (part "PIC-RPX"))
    )
    (comp (ref "T14")
      (value "PIC-RPX")
      (footprint "eagle-import:TEMP-PAD")
      (libsource (lib "eagle-import") (part "PIC-RPX"))
    )
    (comp (ref "T15")
      (value "PIC-OUT")
      (footprint "eagle-import:TEMP-PAD")
      (libsource (lib "eagle-import") (part "PIC-OUT"))
    )
    (comp (ref "T27")
      (value "PIC-OUT")
      (footprint "eagle-import:TEMP-PAD")
      (libsource (lib "eagle-import") (part "PIC-OUT"))
    )
    (comp (ref "T32")
      (value "PIC-OUT")
      (footprint "eagle-import:TEMP-PAD")
      (libsource (lib "eagle-import") (part "PIC-OUT"))
    )
    (comp (ref "T33")
      (value "PIC-OUT")
      (footprint "eagle-import:TEMP-PAD")
      (libsource (lib "eagle-import") (part "PIC-OUT"))
    )
    (comp (ref "T36")
      (value "PIC-OUT")
      (footprint "eagle-import:TEMP-PAD")
      (libsource (lib "eagle-import") (part "PIC-OUT"))
    )
    (comp (ref "T37")
      (value "PIN-AN")
      (footprint "eagle-import:TEMP-PAD")
      (libsource (lib "eagle-import") (part "PIN-AN"))
    )
    (comp (ref "T38")
      (value "PIN-AN")
      (footprint "eagle-import:TEMP-PAD")
      (libsource (lib "eagle-import") (part "PIN-AN"))
    )
    (comp (ref "T39")
      (value "PIN-AN")
      (footprint "eagle-import:TEMP-PAD")
      (libsource (lib "eagle-import") (part "PIN-AN"))
    )
    (comp (ref "T45")
      (value "PIC-RPX")
      (footprint "eagle-import:TEMP-PAD")
      (libsource (lib "eagle-import") (part "PIC-RPX"))
    )
    (comp (ref "TP1")
      (value "DNP-TestPoint")
      (footprint "eagle-import:SMD_ROUND_1MM")
      (libsource (lib "eagle-import") (part "ROUND_SMD1MM"))
    )
    (comp (ref "TP2")
      (value "DNP-TestPoint")
      (footprint "eagle-import:TH_ROUND_14MM08MM")
      (libsource (lib "eagle-import") (part "ROUND_SMDTH1.4MM"))
    )
    (comp (ref "TP4")
      (value "DNP-TestPoint")
      (footprint "eagle-import:TH_ROUND_14MM08MM")
      (libsource (lib "eagle-import") (part "ROUND_SMDTH1.4MM"))
    )
    (comp (ref "X1")
      (value "8MHz-5x3.2mm")
      (footprint "eagle-import:7B")
      (libsource (lib "eagle-import") (part "XTAL-7B"))
    )
  )
  (nets
    (net (code "1") (name "+3.3V") (class "Default")
      (node (ref "C47") (pin "1") (pinfunction "1_1") (pintype "passive"))
      (node (ref "C48") (pin "1") (pinfunction "1_1") (pintype "passive"))
      (node (ref "C49") (pin "1") (pinfunction "1_1") (pintype "passive"))
      (node (ref "C50") (pin "1") (pinfunction "1_1") (pintype "passive"))
      (node (ref "C51") (pin "1") (pinfunction "1_1") (pintype "passive"))
      (node (ref "C52") (pin "1") (pinfunction "1_1") (pintype "passive"))
      (node (ref "C69") (pin "1") (pinfunction "1_1") (pintype "passive"))
      (node (ref "C70") (pin "1") (pinfunction "1_1") (pintype "passive"))
      (node (ref "C81") (pin "+") (pinfunction "+_+") (pintype "passive"))
      (node (ref "IC1") (pin "16") (pinfunction "VDD3_16") (pintype "input"))
      (node (ref "IC1") (pin "2") (pinfunction "VDD2_2") (pintype "input"))
      (node (ref "IC1") (pin "37") (pinfunction "VDD4_37") (pintype "input"))
      (node (ref "IC1") (pin "46") (pinfunction "VDD5_46") (pintype "input"))
      (node (ref "IC1") (pin "55") (pinfunction "VUSB3V3_55") (pintype "input"))
      (node (ref "IC1") (pin "62") (pinfunction "VDD6_62") (pintype "input"))
      (node (ref "IC1") (pin "86") (pinfunction "VDD1_86") (pintype "input"))
      (node (ref "J17") (pin "2") (pinfunction "2_2") (pintype "passive"))
      (node (ref "L13") (pin "1") (pinfunction "1_1") (pintype "passive"))
      (node (ref "R103") (pin "2") (pinfunction "2_2") (pintype "passive"))
      (node (ref "R105") (pin "2") (pinfunction "2_2") (pintype "passive"))
      (node (ref "R106") (pin "2") (pinfunction "2_2") (pintype "passive"))
      (node (ref "R129") (pin "1") (pinfunction "1_1") (pintype "passive"))
      (node (ref "R28") (pin "2") (pinfunction "2_2") (pintype "passive"))
      (node (ref "R65") (pin "1") (pinfunction "1_1") (pintype "passive"))
      (node (ref "R82") (pin "1") (pinfunction "1_1") (pintype "passive"))
      (node (ref "R91") (pin "2") (pinfunction "2_2") (pintype "passive"))
    )
    (net (code "2") (name "+3.3V{slash}1") (class "Default")
      (node (ref "C27") (pin "1") (pinfunction "1_1") (pintype "passive"))
      (node (ref "C28") (pin "1") (pinfunction "1_1") (pintype "passive"))
      (node (ref "IC11") (pin "2") (pinfunction "A1_2") (pintype "input"))
      (node (ref "IC11") (pin "8") (pinfunction "VCC_8") (pintype "input"))
      (node (ref "IC7") (pin "8") (pinfunction "VCC_8") (pintype "input"))
      (node (ref "IC9") (pin "3") (pinfunction "/WP_3") (pintype "input"))
      (node (ref "IC9") (pin "7") (pinfunction "/HOLD_7") (pintype "input"))
      (node (ref "IC9") (pin "8") (pinfunction "VCC_8") (pintype "input"))
      (node (ref "Q2") (pin "3") (pinfunction "D_3") (pintype "passive"))
      (node (ref "Q2") (pin "P2") (pinfunction "D1_P2") (pintype "passive"))
      (node (ref "R18") (pin "1") (pinfunction "1_1") (pintype "passive"))
      (node (ref "R25") (pin "2") (pinfunction "2_2") (pintype "passive"))
      (node (ref "R26") (pin "1") (pinfunction "1_1") (pintype "passive"))
      (node (ref "R27") (pin "1") (pinfunction "1_1") (pintype "passive"))
    )
    (net (code "3") (name "+3.3V{slash}2") (class "Default")
      (node (ref "C41") (pin "1") (pinfunction "1_1") (pintype "passive"))
      (node (ref "C86") (pin "+") (pinfunction "+_+") (pintype "passive"))
      (node (ref "IC12") (pin "8") (pinfunction "VCC_8") (pintype "input"))
      (node (ref "Q1") (pin "3") (pinfunction "D_3") (pintype "passive"))
      (node (ref "Q1") (pin "P2") (pinfunction "D1_P2") (pintype "passive"))
      (node (ref "R30") (pin "2") (pinfunction "2_2") (pintype "passive"))
      (node (ref "R34") (pin "1") (pinfunction "1_1") (pintype "passive"))
      (node (ref "R72") (pin "1") (pinfunction "1_1") (pintype "passive"))
      (node (ref "R73") (pin "2") (pinfunction "2_2") (pintype "passive"))
    )
    (net (code "4") (name "/A+") (class "Default")
      (node (ref "IC14") (pin "3") (pinfunction "3_3") (pintype "passive"))
      (node (ref "J3") (pin "4") (pinfunction "4_4") (pintype "passive"))
      (node (ref "J4") (pin "4") (pinfunction "4_4") (pintype "passive"))
      (node (ref "L8") (pin "2") (pinfunction "2_2") (pintype "passive"))
    )
    (net (code "5") (name "/A++") (class "Default")
      (node (ref "IC12") (pin "6") (pinfunction "A_6") (pintype "bidirectional"))
      (node (ref "L8") (pin "1") (pinfunction "1_1") (pintype "passive"))
      (node (ref "R32") (pin "2") (pinfunction "2_2") (pintype "passive"))
      (node (ref "R34") (pin "2") (pinfunction "2_2") (pintype "passive"))
    )
    (net (code "6") (name "/ACT-L-SENSE") (class "Default")
      (node (ref "R1") (pin "7") (pinfunction "2_7") (pintype "passive"))
      (node (ref "R1") (pin "8") (pinfunction "2_8") (pintype "passive"))
    )
    (net (code "7") (name "/ACT-L-SW") (class "Default")
      (node (ref "C44") (pin "1") (pinfunction "1_1") (pintype "passive"))
      (node (ref "J14") (pin "2") (pinfunction "2_2") (pintype "passive"))
      (node (ref "R1") (pin "1") (pinfunction "1_1") (pintype "passive"))
      (node (ref "R2") (pin "8") (pinfunction "2_8") (pintype "passive"))
    )
    (net (code "8") (name "/ACT-R-SENSE") (class "Default")
      (node (ref "R1") (pin "5") (pinfunction "2_5") (pintype "passive"))
      (node (ref "R1") (pin "6") (pinfunction "2_6") (pintype "passive"))
    )
    (net (code "9") (name "/ACT-R-SW") (class "Default")
      (node (ref "C3") (pin "1") (pinfunction "1_1") (pintype "passive"))
      (node (ref "J15") (pin "2") (pinfunction "2_2") (pintype "passive"))
      (node (ref "R1") (pin "3") (pinfunction "1_3") (pintype "passive"))
      (node (ref "R2") (pin "7") (pinfunction "2_7") (pintype "passive"))
    )
    (net (code "10") (name "/ACT_EN") (class "Default")
      (node (ref "R11") (pin "5") (pinfunction "2_5") (pintype "passive"))
      (node (ref "R11") (pin "6") (pinfunction "2_6") (pintype "passive"))
      (node (ref "R7") (pin "4") (pinfunction "1_4") (pintype "passive"))
    )
    (net (code "11") (name "/ACT_L+") (class "Default")
      (node (ref "IC2") (pin "31") (pinfunction "OUT1A_31") (pintype "output"))
      (node (ref "J14") (pin "1") (pinfunction "1_1") (pintype "passive"))
    )
    (net (code "12") (name "/ACT_L-") (class "Default")
      (node (ref "IC2") (pin "23") (pinfunction "OUT2A_23") (pintype "output"))
      (node (ref "J14") (pin "3") (pinfunction "3_3") (pintype "passive"))
    )
    (net (code "13") (name "/ACT_L1") (class "Default")
      (node (ref "IC2") (pin "27") (pinfunction "IN1_A_27") (pintype "input"))
      (node (ref "R10") (pin "5") (pinfunction "2_5") (pintype "passive"))
    )
    (net (code "14") (name "/ACT_L2") (class "Default")
      (node (ref "IC2") (pin "28") (pinfunction "IN2_A_28") (pintype "input"))
      (node (ref "R10") (pin "6") (pinfunction "2_6") (pintype "passive"))
    )
    (net (code "15") (name "/ACT_R+") (class "Default")
      (node (ref "IC2") (pin "9") (pinfunction "OUT1B_9") (pintype "output"))
      (node (ref "J15") (pin "1") (pinfunction "1_1") (pintype "passive"))
    )
    (net (code "16") (name "/ACT_R-") (class "Default")
      (node (ref "IC2") (pin "19") (pinfunction "OUT2B_19") (pintype "output"))
      (node (ref "J15") (pin "3") (pinfunction "3_3") (pintype "passive"))
    )
    (net (code "17") (name "/ACT_R1") (class "Default")
      (node (ref "IC2") (pin "13") (pinfunction "IN1_B_13") (pintype "input"))
      (node (ref "R10") (pin "7") (pinfunction "2_7") (pintype "passive"))
    )
    (net (code "18") (name "/ACT_R2") (class "Default")
      (node (ref "IC2") (pin "14") (pinfunction "IN2_B_14") (pintype "input"))
      (node (ref "R10") (pin "8") (pinfunction "2_8") (pintype "passive"))
    )
    (net (code "19") (name "/B-") (class "Default")
      (node (ref "IC14") (pin "2") (pinfunction "2_2") (pintype "passive"))
      (node (ref "J3") (pin "5") (pinfunction "5_5") (pintype "passive"))
      (node (ref "J4") (pin "5") (pinfunction "5_5") (pintype "passive"))
      (node (ref "L7") (pin "2") (pinfunction "2_2") (pintype "passive"))
    )
    (net (code "20") (name "/B--") (class "Default")
      (node (ref "IC12") (pin "7") (pinfunction "B_7") (pintype "bidirectional"))
      (node (ref "L7") (pin "1") (pinfunction "1_1") (pintype "passive"))
      (node (ref "R31") (pin "1") (pinfunction "1_1") (pintype "passive"))
      (node (ref "R32") (pin "1") (pinfunction "1_1") (pintype "passive"))
    )
    (net (code "21") (name "/CURR-SENSE") (class "Default")
      (node (ref "C66") (pin "1") (pinfunction "1_1") (pintype "passive"))
      (node (ref "IC1") (pin "14") (pinfunction "AN19/C2INC/RPG9/PMA2/RG9_14") (pintype "bidirectional"))
      (node (ref "O8") (pin "P$1") (pinfunction "TP_P$1") (pintype "passive"))
      (node (ref "R102") (pin "2") (pinfunction "2_2") (pintype "passive"))
      (node (ref "T39") (pin "P$1") (pinfunction "TP_P$1") (pintype "passive"))
    )
    (net (code "22") (name "/D+") (class "Default")
      (node (ref "IC1") (pin "57") (pinfunction "D+/RG2_57") (pintype "bidirectional"))
      (node (ref "IC15") (pin "3") (pinfunction "3_3") (pintype "passive"))
      (node (ref "J12") (pin "3_D+") (pinfunction "D+_3_D+") (pintype "bidirectional"))
    )
    (net (code "23") (name "/D-") (class "Default")
      (node (ref "IC1") (pin "56") (pinfunction "D-/RG3_56") (pintype "bidirectional"))
      (node (ref "IC15") (pin "2") (pinfunction "2_2") (pintype "passive"))
      (node (ref "J12") (pin "2_D-") (pinfunction "D-_2_D-") (pintype "bidirectional"))
    )
    (net (code "24") (name "/DOOR_L") (class "Default")
      (node (ref "R50") (pin "2") (pinfunction "1_2") (pintype "passive"))
      (node (ref "R50") (pin "3") (pinfunction "1_3") (pintype "passive"))
    )
    (net (code "25") (name "/DOOR_L_SW") (class "Default")
      (node (ref "C12") (pin "1") (pinfunction "1_1") (pintype "passive"))
      (node (ref "J14") (pin "4") (pinfunction "4_4") (pintype "passive"))
      (node (ref "R50") (pin "7") (pinfunction "2_7") (pintype "passive"))
      (node (ref "R6") (pin "2") (pinfunction "2_2") (pintype "passive"))
    )
    (net (code "26") (name "/DOOR_ON") (class "Default")
      (node (ref "Q3") (pin "5") (pinfunction "Q1G_5") (pintype "input"))
      (node (ref "R9") (pin "7") (pinfunction "2_7") (pintype "passive"))
    )
    (net (code "27") (name "/DOOR_R") (class "Default")
      (node (ref "R50") (pin "1") (pinfunction "1_1") (pintype "passive"))
      (node (ref "R50") (pin "4") (pinfunction "1_4") (pintype "passive"))
    )
    (net (code "28") (name "/DOOR_R_SW") (class "Default")
      (node (ref "C4") (pin "1") (pinfunction "1_1") (pintype "passive"))
      (node (ref "J15") (pin "4") (pinfunction "4_4") (pintype "passive"))
      (node (ref "R50") (pin "8") (pinfunction "2_8") (pintype "passive"))
      (node (ref "R8") (pin "2") (pinfunction "2_2") (pintype "passive"))
    )
    (net (code "29") (name "/LAN-CTL") (class "Default")
      (node (ref "IC1") (pin "84") (pinfunction "PMD15/RD7_84") (pintype "bidirectional"))
      (node (ref "IC12") (pin "2") (pinfunction "/RE_2") (pintype "input"))
      (node (ref "IC12") (pin "3") (pinfunction "DE_3") (pintype "input"))
      (node (ref "O31") (pin "P$1") (pinfunction "TP_P$1") (pintype "passive"))
      (node (ref "R71") (pin "1") (pinfunction "1_1") (pintype "passive"))
      (node (ref "T15") (pin "P$1") (pinfunction "TP_P$1") (pintype "passive"))
    )
    (net (code "30") (name "/LAN-RX") (class "Default")
      (node (ref "IC1") (pin "88") (pinfunction "RPF1/PMD10/RF1_88") (pintype "bidirectional"))
      (node (ref "IC12") (pin "1") (pinfunction "R_1") (pintype "output"))
      (node (ref "O29") (pin "P$1") (pinfunction "TP_P$1") (pintype "passive"))
      (node (ref "R72") (pin "2") (pinfunction "2_2") (pintype "passive"))
      (node (ref "T13") (pin "P$1") (pinfunction "TP_P$1") (pintype "passive"))
    )
    (net (code "31") (name "/LAN-TX") (class "Default")
      (node (ref "IC1") (pin "87") (pinfunction "RPF0/PMD11/RF0_87") (pintype "bidirectional"))
      (node (ref "IC12") (pin "4") (pinfunction "D_4") (pintype "input"))
      (node (ref "O30") (pin "P$1") (pinfunction "TP_P$1") (pintype "passive"))
      (node (ref "R73") (pin "1") (pinfunction "1_1") (pintype "passive"))
      (node (ref "T14") (pin "P$1") (pinfunction "TP_P$1") (pintype "passive"))
    )
    (net (code "32") (name "/LED-PIC") (class "Default")
      (node (ref "IC1") (pin "1") (pinfunction "RG15_1") (pintype "bidirectional"))
      (node (ref "O1") (pin "P$1") (pinfunction "TP_P$1") (pintype "passive"))
      (node (ref "R29") (pin "1") (pinfunction "1_1") (pintype "passive"))
      (node (ref "T36") (pin "P$1") (pinfunction "TP_P$1") (pintype "passive"))
      (node (ref "TP4") (pin "P$1") (pinfunction "TP_P$1") (pintype "passive"))
    )
    (net (code "33") (name "/PGC") (class "Default")
      (node (ref "IC1") (pin "24") (pinfunction "PGEC1/AN1/RPB1/CTED12/RB1_24") (pintype "bidirectional"))
      (node (ref "J17") (pin "5") (pinfunction "5_5") (pintype "passive"))
    )
    (net (code "34") (name "/PGD") (class "Default")
      (node (ref "IC1") (pin "25") (pinfunction "PGED1/AN0/RPB0/RB0_25") (pintype "bidirectional"))
      (node (ref "J17") (pin "4") (pinfunction "4_4") (pintype "passive"))
      (node (ref "R130") (pin "2") (pinfunction "2_2") (pintype "passive"))
    )
    (net (code "35") (name "/POWER-GOOD") (class "Default")
      (node (ref "IC6") (pin "4") (pinfunction "OUT_4") (pintype "output"))
      (node (ref "R130") (pin "1") (pinfunction "1_1") (pintype "passive"))
      (node (ref "T45") (pin "P$1") (pinfunction "TP_P$1") (pintype "passive"))
      (node (ref "TP2") (pin "P$1") (pinfunction "TP_P$1") (pintype "passive"))
    )
    (net (code "36") (name "/REF-EN") (class "Default")
      (node (ref "IC1") (pin "28") (pinfunction "VREF-/CVREF-/PMA7/RA9_28") (pintype "bidirectional"))
      (node (ref "R93") (pin "1") (pinfunction "1_1") (pintype "passive"))
    )
    (net (code "37") (name "/REF2,5V") (class "Default")
      (node (ref "C57") (pin "1") (pinfunction "1_1") (pintype "passive"))
      (node (ref "IC1") (pin "29") (pinfunction "VREF+/CVREF+/PMA6/RA10_29") (pintype "bidirectional"))
      (node (ref "IC13") (pin "2") (pinfunction "VOUT_2") (pintype "bidirectional"))
    )
    (net (code "38") (name "/SCL1-EEPROM") (class "Default")
      (node (ref "IC1") (pin "66") (pinfunction "SCL1/RPA14/RA14_66") (pintype "bidirectional"))
      (node (ref "IC11") (pin "6") (pinfunction "SCL_6") (pintype "input"))
      (node (ref "IC7") (pin "6") (pinfunction "SCL_6") (pintype "input"))
      (node (ref "R26") (pin "2") (pinfunction "2_2") (pintype "passive"))
    )
    (net (code "39") (name "/SCLK2-SPI") (class "Default")
      (node (ref "IC1") (pin "10") (pinfunction "AN16/C1IND/RPG6/SCK2/PMA5/RG6_10") (pintype "bidirectional"))
      (node (ref "IC9") (pin "6") (pinfunction "C_6") (pintype "input"))
    )
    (net (code "40") (name "/SD-CS") (class "Default")
      (node (ref "IC1") (pin "9") (pinfunction "RPC4/CTED7/RC4_9") (pintype "bidirectional"))
      (node (ref "O5") (pin "P$1") (pinfunction "TP_P$1") (pintype "passive"))
    )
    (net (code "41") (name "/SDA1-EEPROM") (class "Default")
      (node (ref "IC1") (pin "67") (pinfunction "SDA1/RPA15/RA15_67") (pintype "bidirectional"))
      (node (ref "IC11") (pin "5") (pinfunction "SDA_5") (pintype "bidirectional"))
      (node (ref "IC7") (pin "5") (pinfunction "SDA_5") (pintype "bidirectional"))
      (node (ref "R27") (pin "2") (pinfunction "2_2") (pintype "passive"))
    )
    (net (code "42") (name "/SDI2-MISO") (class "Default")
      (node (ref "IC1") (pin "22") (pinfunction "PGED3/AN3/C2INA/RPB3/RB3_22") (pintype "bidirectional"))
      (node (ref "IC9") (pin "2") (pinfunction "Q_2") (pintype "bidirectional"))
      (node (ref "O13") (pin "P$1") (pinfunction "TP_P$1") (pintype "passive"))
    )
    (net (code "43") (name "/SDO2-MOSI") (class "Default")
      (node (ref "IC1") (pin "20") (pinfunction "AN5/C1INA/RPB5/RB5_20") (pintype "bidirectional"))
      (node (ref "IC9") (pin "5") (pinfunction "D_5") (pintype "input"))
      (node (ref "O12") (pin "P$1") (pinfunction "TP_P$1") (pintype "passive"))
    )
    (net (code "44") (name "/VBAT-LAN") (class "Default")
      (node (ref "D3") (pin "C") (pinfunction "C_C") (pintype "passive"))
      (node (ref "J3") (pin "1") (pinfunction "1_1") (pintype "passive"))
      (node (ref "J3") (pin "3") (pinfunction "3_3") (pintype "passive"))
      (node (ref "J4") (pin "1") (pinfunction "1_1") (pintype "passive"))
      (node (ref "J4") (pin "3") (pinfunction "3_3") (pintype "passive"))
      (node (ref "L11") (pin "2") (pinfunction "2_2") (pintype "passive"))
    )
    (net (code "45") (name "/VBAT-LAN-F") (class "Default")
      (node (ref "C33") (pin "1") (pinfunction "1_1") (pintype "passive"))
      (node (ref "C34") (pin "1") (pinfunction "1_1") (pintype "passive"))
      (node (ref "D6") (pin "K") (pinfunction "K_K") (pintype "passive"))
      (node (ref "L11") (pin "1") (pinfunction "1_1") (pintype "passive"))
      (node (ref "Q5") (pin "2") (pinfunction "S_2") (pintype "passive"))
      (node (ref "Q5") (pin "5") (pinfunction "S_5") (pintype "passive"))
      (node (ref "R132") (pin "1") (pinfunction "1_1") (pintype "passive"))
      (node (ref "R36") (pin "2") (pinfunction "2_2") (pintype "passive"))
      (node (ref "R38") (pin "2") (pinfunction "2_2") (pintype "passive"))
      (node (ref "R42") (pin "1") (pinfunction "1_1") (pintype "passive"))
      (node (ref "R45") (pin "1") (pinfunction "1_1") (pintype "passive"))
      (node (ref "R94") (pin "1") (pinfunction "1_1") (pintype "passive"))
    )
    (net (code "46") (name "/VBAT-ON") (class "Default")
      (node (ref "IC1") (pin "52") (pinfunction "RPF2/RF2_52") (pintype "bidirectional"))
      (node (ref "O42") (pin "P$1") (pinfunction "TP_P$1") (pintype "passive"))
      (node (ref "Q4") (pin "2") (pinfunction "G_2") (pintype "passive"))
      (node (ref "R132") (pin "2") (pinfunction "2_2") (pintype "passive"))
      (node (ref "R41") (pin "1") (pinfunction "1_1") (pintype "passive"))
      (node (ref "T5") (pin "P$1") (pinfunction "TP_P$1") (pintype "passive"))
    )
    (net (code "47") (name "/VBAT-SENSE") (class "Default")
      (node (ref "C64") (pin "1") (pinfunction "1_1") (pintype "passive"))
      (node (ref "IC1") (pin "26") (pinfunction "PGEC2/AN6/RPB6/RB6_26") (pintype "bidirectional"))
      (node (ref "O15") (pin "P$1") (pinfunction "TP_P$1") (pintype "passive"))
      (node (ref "R100") (pin "1") (pinfunction "1_1") (pintype "passive"))
      (node (ref "T37") (pin "P$1") (pinfunction "TP_P$1") (pintype "passive"))
    )
    (net (code "48") (name "/VBATLAN-SENSE") (class "Default")
      (node (ref "C36") (pin "1") (pinfunction "1_1") (pintype "passive"))
      (node (ref "IC1") (pin "27") (pinfunction "PGED2/AN7/RPB7/CTED3/RB7_27") (pintype "bidirectional"))
      (node (ref "O16") (pin "P$1") (pinfunction "TP_P$1") (pintype "passive"))
      (node (ref "R101") (pin "1") (pinfunction "1_1") (pintype "passive"))
      (node (ref "T38") (pin "P$1") (pinfunction "TP_P$1") (pintype "passive"))
    )
    (net (code "49") (name "/VBUS") (class "Default")
      (node (ref "IC1") (pin "54") (pinfunction "VBUS_54") (pintype "input"))
      (node (ref "R128") (pin "2") (pinfunction "2_2") (pintype "passive"))
    )
    (net (code "50") (name "/VPS-ON") (class "Default")
      (node (ref "IC1") (pin "53") (pinfunction "RPF8/RF8_53") (pintype "bidirectional"))
      (node (ref "O41") (pin "P$1") (pinfunction "TP_P$1") (pintype "passive"))
      (node (ref "Q4") (pin "5") (pinfunction "G_5") (pintype "passive"))
      (node (ref "R44") (pin "1") (pinfunction "1_1") (pintype "passive"))
      (node (ref "T7") (pin "P$1") (pinfunction "TP_P$1") (pintype "passive"))
    )
    (net (code "51") (name "/VPS-PWR") (class "Default")
      (node (ref "D4") (pin "C") (pinfunction "C_C") (pintype "passive"))
      (node (ref "J3") (pin "6") (pinfunction "6_6") (pintype "passive"))
      (node (ref "J4") (pin "6") (pinfunction "6_6") (pintype "passive"))
      (node (ref "L10") (pin "2") (pinfunction "2_2") (pintype "passive"))
    )
    (net (code "52") (name "/VPS-PWR-F") (class "Default")
      (node (ref "L10") (pin "1") (pinfunction "1_1") (pintype "passive"))
      (node (ref "Q5") (pin "4") (pinfunction "D_4") (pintype "passive"))
      (node (ref "R23") (pin "2") (pinfunction "2_2") (pintype "passive"))
    )
    (net (code "53") (name "/VPS-SENSE") (class "Default")
      (node (ref "C65") (pin "1") (pinfunction "1_1") (pintype "passive"))
      (node (ref "IC1") (pin "12") (pinfunction "AN18/C2IND/RPG8/PMA3/RG8_12") (pintype "bidirectional"))
      (node (ref "O7") (pin "P$1") (pinfunction "TP_P$1") (pintype "passive"))
      (node (ref "R48") (pin "2") (pinfunction "2_2") (pintype "passive"))
      (node (ref "R49") (pin "1") (pinfunction "1_1") (pintype "passive"))
      (node (ref "T3") (pin "P$1") (pinfunction "TP_P$1") (pintype "passive"))
    )
    (net (code "54") (name "/{slash}3.3V1PWRON") (class "Default")
      (node (ref "IC1") (pin "21") (pinfunction "AN4/C1INB/USBOEN/RB4_21") (pintype "bidirectional"))
      (node (ref "O44") (pin "P$1") (pinfunction "TP_P$1") (pintype "passive"))
      (node (ref "R24") (pin "2") (pinfunction "2_2") (pintype "passive"))
      (node (ref "T32") (pin "P$1") (pinfunction "TP_P$1") (pintype "passive"))
    )
    (net (code "55") (name "/{slash}3.3V2PWRON") (class "Default")
      (node (ref "IC1") (pin "96") (pinfunction "TRD1/RG12_96") (pintype "bidirectional"))
      (node (ref "O23") (pin "P$1") (pinfunction "TP_P$1") (pintype "passive"))
      (node (ref "R75") (pin "2") (pinfunction "2_2") (pintype "passive"))
      (node (ref "T33") (pin "P$1") (pinfunction "TP_P$1") (pintype "passive"))
    )
    (net (code "56") (name "/{slash}FMEM1-CS") (class "Default")
      (node (ref "IC1") (pin "11") (pinfunction "AN17/C1INC/RPG7/PMA4/RG7_11") (pintype "bidirectional"))
      (node (ref "IC9") (pin "1") (pinfunction "/S_1") (pintype "input"))
      (node (ref "O6") (pin "P$1") (pinfunction "TP_P$1") (pintype "passive"))
      (node (ref "R25") (pin "1") (pinfunction "1_1") (pintype "passive"))
      (node (ref "T27") (pin "P$1") (pinfunction "TP_P$1") (pintype "passive"))
    )
    (net (code "57") (name "/{slash}MCLR") (class "Default")
      (node (ref "IC1") (pin "13") (pinfunction "~{MCLR}_13") (pintype "input"))
      (node (ref "J17") (pin "1") (pinfunction "1_1") (pintype "passive"))
      (node (ref "R90") (pin "2") (pinfunction "2_2") (pintype "passive"))
    )
    (net (code "58") (name "DGND") (class "Default")
      (node (ref "C22") (pin "2") (pinfunction "2_2") (pintype "passive"))
      (node (ref "C23") (pin "2") (pinfunction "2_2") (pintype "passive"))
      (node (ref "C24") (pin "1") (pinfunction "1_1") (pintype "passive"))
      (node (ref "C27") (pin "2") (pinfunction "2_2") (pintype "passive"))
      (node (ref "C28") (pin "2") (pinfunction "2_2") (pintype "passive"))
      (node (ref "C29") (pin "2") (pinfunction "2_2") (pintype "passive"))
      (node (ref "C30") (pin "2") (pinfunction "2_2") (pintype "passive"))
      (node (ref "C31") (pin "-") (pinfunction "-_-") (pintype "passive"))
      (node (ref "C35") (pin "2") (pinfunction "2_2") (pintype "passive"))
      (node (ref "C36") (pin "2") (pinfunction "2_2") (pintype "passive"))
      (node (ref "C40") (pin "2") (pinfunction "2_2") (pintype "passive"))
      (node (ref "C41") (pin "2") (pinfunction "2_2") (pintype "passive"))
      (node (ref "C47") (pin "2") (pinfunction "2_2") (pintype "passive"))
      (node (ref "C48") (pin "2") (pinfunction "2_2") (pintype "passive"))
      (node (ref "C49") (pin "2") (pinfunction "2_2") (pintype "passive"))
      (node (ref "C50") (pin "2") (pinfunction "2_2") (pintype "passive"))
      (node (ref "C51") (pin "2") (pinfunction "2_2") (pintype "passive"))
      (node (ref "C52") (pin "2") (pinfunction "2_2") (pintype "passive"))
      (node (ref "C53") (pin "2") (pinfunction "2_2") (pintype "passive"))
      (node (ref "C54") (pin "-") (pinfunction "-_-") (pintype "passive"))
      (node (ref "C55") (pin "2") (pinfunction "2_2") (pintype "passive"))
      (node (ref "C56") (pin "-") (pinfunction "-_-") (pintype "passive"))
      (node (ref "C57") (pin "2") (pinfunction "2_2") (pintype "passive"))
      (node (ref "C58") (pin "2") (pinfunction "2_2") (pintype "passive"))
      (node (ref "C59") (pin "2") (pinfunction "2_2") (pintype "passive"))
      (node (ref "C60") (pin "2") (pinfunction "2_2") (pintype "passive"))
      (node (ref "C61") (pin "2") (pinfunction "2_2") (pintype "passive"))
      (node (ref "C62") (pin "2") (pinfunction "2_2") (pintype "passive"))
      (node (ref "C63") (pin "2") (pinfunction "2_2") (pintype "passive"))
      (node (ref "C64") (pin "2") (pinfunction "2_2") (pintype "passive"))
      (node (ref "C65") (pin "2") (pinfunction "2_2") (pintype "passive"))
      (node (ref "C66") (pin "2") (pinfunction "2_2") (pintype "passive"))
      (node (ref "C67") (pin "2") (pinfunction "2_2") (pintype "passive"))
      (node (ref "C81") (pin "-") (pinfunction "-_-") (pintype "passive"))
      (node (ref "C83") (pin "2") (pinfunction "2_2") (pintype "passive"))
      (node (ref "C84") (pin "2") (pinfunction "2_2") (pintype "passive"))
      (node (ref "C85") (pin "2") (pinfunction "2_2") (pintype "passive"))
      (node (ref "C86") (pin "-") (pinfunction "-_-") (pintype "passive"))
      (node (ref "C88") (pin "2") (pinfunction "2_2") (pintype "passive"))
      (node (ref "D2") (pin "-") (pinfunction "A_-") (pintype "passive"))
      (node (ref "D5") (pin "K") (pinfunction "K_K") (pintype "passive"))
      (node (ref "D7") (pin "A") (pinfunction "A_A") (pintype "passive"))
      (node (ref "IC1") (pin "15") (pinfunction "VSS2_15") (pintype "input"))
      (node (ref "IC1") (pin "31") (pinfunction "AVSS_31") (pintype "input"))
      (node (ref "IC1") (pin "36") (pinfunction "VSS3_36") (pintype "input"))
      (node (ref "IC1") (pin "45") (pinfunction "VSS4_45") (pintype "input"))
      (node (ref "IC1") (pin "65") (pinfunction "VSS5_65") (pintype "input"))
      (node (ref "IC1") (pin "75") (pinfunction "VSS1_75") (pintype "input"))
      (node (ref "IC10") (pin "1") (pinfunction "GND_1") (pintype "input"))
      (node (ref "IC10") (pin "2") (pinfunction "GND1_2") (pintype "input"))
      (node (ref "IC11") (pin "1") (pinfunction "A0_1") (pintype "input"))
      (node (ref "IC11") (pin "3") (pinfunction "A2_3") (pintype "input"))
      (node (ref "IC11") (pin "4") (pinfunction "GND_4") (pintype "input"))
      (node (ref "IC12") (pin "5") (pinfunction "GND_5") (pintype "input"))
      (node (ref "IC13") (pin "3") (pinfunction "GND_3") (pintype "bidirectional"))
      (node (ref "IC15") (pin "1") (pinfunction "1_1") (pintype "input"))
      (node (ref "IC16") (pin "4") (pinfunction "V-_4") (pintype "input"))
      (node (ref "IC6") (pin "2") (pinfunction "GND_2") (pintype "input"))
      (node (ref "IC7") (pin "1") (pinfunction "A0_1") (pintype "input"))
      (node (ref "IC7") (pin "2") (pinfunction "A1_2") (pintype "input"))
      (node (ref "IC7") (pin "3") (pinfunction "A2_3") (pintype "input"))
      (node (ref "IC7") (pin "4") (pinfunction "GND_4") (pintype "input"))
      (node (ref "IC7") (pin "7") (pinfunction "WP_7") (pintype "input"))
      (node (ref "IC8") (pin "10") (pinfunction "SYNC_10") (pintype "bidirectional"))
      (node (ref "IC8") (pin "EP") (pinfunction "GND_EP") (pintype "bidirectional"))
      (node (ref "IC9") (pin "4") (pinfunction "GND_4") (pintype "input"))
      (node (ref "J12") (pin "4_GND") (pinfunction "GND_4_GND") (pintype "bidirectional"))
      (node (ref "J12") (pin "SH1") (pinfunction "GND_SH1_SH1") (pintype "bidirectional"))
      (node (ref "J12") (pin "SH2") (pinfunction "GND_SH2_SH2") (pintype "bidirectional"))
      (node (ref "J17") (pin "3") (pinfunction "3_3") (pintype "passive"))
      (node (ref "L12") (pin "1") (pinfunction "1_1") (pintype "passive"))
      (node (ref "L2") (pin "2") (pinfunction "2_2") (pintype "passive"))
      (node (ref "PCB1") (pin "PAD_GND_1") (pinfunction "PAD_GND_1_PAD_GND_1") (pintype "bidirectional"))
      (node (ref "PCB1") (pin "PAD_GND_2") (pinfunction "PAD_GND_2_PAD_GND_2") (pintype "bidirectional"))
      (node (ref "PCB1") (pin "PAD_GND_3") (pinfunction "PAD_GND_3_PAD_GND_3") (pintype "bidirectional"))
      (node (ref "PCB1") (pin "PAD_GND_4") (pinfunction "PAD_GND_4_PAD_GND_4") (pintype "bidirectional"))
      (node (ref "R17") (pin "2") (pinfunction "2_2") (pintype "passive"))
      (node (ref "R19") (pin "2") (pinfunction "2_2") (pintype "passive"))
      (node (ref "R21") (pin "2") (pinfunction "2_2") (pintype "passive"))
      (node (ref "R31") (pin "2") (pinfunction "2_2") (pintype "passive"))
      (node (ref "R40") (pin "1") (pinfunction "1_1") (pintype "passive"))
      (node (ref "R41") (pin "2") (pinfunction "2_2") (pintype "passive"))
      (node (ref "R43") (pin "1") (pinfunction "1_1") (pintype "passive"))
      (node (ref "R44") (pin "2") (pinfunction "2_2") (pintype "passive"))
      (node (ref "R46") (pin "1") (pinfunction "1_1") (pintype "passive"))
      (node (ref "R48") (pin "1") (pinfunction "1_1") (pintype "passive"))
      (node (ref "R71") (pin "2") (pinfunction "2_2") (pintype "passive"))
      (node (ref "R96") (pin "2") (pinfunction "2_2") (pintype "passive"))
      (node (ref "R99") (pin "2") (pinfunction "2_2") (pintype "passive"))
    )
    (net (code "59") (name "Net-(C24-Pad2)") (class "Default")
      (node (ref "C24") (pin "2") (pinfunction "2_2") (pintype "passive"))
      (node (ref "R77") (pin "2") (pinfunction "2_2") (pintype "passive"))
    )
    (net (code "60") (name "Net-(C39-Pad1)") (class "Default")
      (node (ref "C39") (pin "1") (pinfunction "1_1") (pintype "passive"))
      (node (ref "IC14") (pin "4") (pinfunction "4_4") (pintype "input"))
      (node (ref "R30") (pin "1") (pinfunction "1_1") (pintype "passive"))
    )
    (net (code "61") (name "Net-(C39-Pad2)") (class "Default")
      (node (ref "C39") (pin "2") (pinfunction "2_2") (pintype "passive"))
      (node (ref "D3") (pin "A") (pinfunction "A_A") (pintype "passive"))
      (node (ref "D4") (pin "A") (pinfunction "A_A") (pintype "passive"))
      (node (ref "IC14") (pin "1") (pinfunction "1_1") (pintype "input"))
      (node (ref "J3") (pin "2") (pinfunction "2_2") (pintype "passive"))
      (node (ref "J3") (pin "7") (pinfunction "7_7") (pintype "passive"))
      (node (ref "J3") (pin "8") (pinfunction "8_8") (pintype "passive"))
      (node (ref "J4") (pin "2") (pinfunction "2_2") (pintype "passive"))
      (node (ref "J4") (pin "7") (pinfunction "7_7") (pintype "passive"))
      (node (ref "J4") (pin "8") (pinfunction "8_8") (pintype "passive"))
      (node (ref "L12") (pin "2") (pinfunction "2_2") (pintype "passive"))
    )
    (net (code "62") (name "Net-(C40-Pad1)") (class "Default")
      (node (ref "C40") (pin "1") (pinfunction "1_1") (pintype "passive"))
      (node (ref "R90") (pin "1") (pinfunction "1_1") (pintype "passive"))
      (node (ref "R91") (pin "1") (pinfunction "1_1") (pintype "passive"))
    )
    (net (code "63") (name "Net-(D1-K)") (class "Default")
      (node (ref "C37") (pin "2") (pinfunction "2_2") (pintype "passive"))
      (node (ref "D1") (pin "2") (pinfunction "K_2") (pintype "passive"))
      (node (ref "IC2") (pin "17") (pinfunction "VBOOT_17") (pintype "input"))
    )
    (net (code "64") (name "Net-(D1-KA)") (class "Default")
      (node (ref "C2") (pin "1") (pinfunction "1_1") (pintype "passive"))
      (node (ref "D1") (pin "3") (pinfunction "KA_3") (pintype "passive"))
    )
    (net (code "65") (name "Net-(D2-C)") (class "Default")
      (node (ref "C26") (pin "1") (pinfunction "1_1") (pintype "passive"))
      (node (ref "C30") (pin "1") (pinfunction "1_1") (pintype "passive"))
      (node (ref "C31") (pin "+") (pinfunction "+_+") (pintype "passive"))
      (node (ref "D2") (pin "+") (pinfunction "C_+") (pintype "passive"))
      (node (ref "IC8") (pin "1") (pinfunction "BD_1") (pintype "bidirectional"))
      (node (ref "L9") (pin "2") (pinfunction "2_2") (pintype "passive"))
      (node (ref "R129") (pin "2") (pinfunction "2_2") (pintype "passive"))
      (node (ref "R20") (pin "1") (pinfunction "1_1") (pintype "passive"))
    )
    (net (code "66") (name "Net-(D5-PadA)") (class "Default")
      (node (ref "D5") (pin "A") (pinfunction "A_A") (pintype "passive"))
      (node (ref "R29") (pin "2") (pinfunction "2_2") (pintype "passive"))
    )
    (net (code "67") (name "Net-(D9-C)") (class "Default")
      (node (ref "D9") (pin "3") (pinfunction "C_3") (pintype "passive"))
      (node (ref "R2") (pin "1") (pinfunction "1_1") (pintype "passive"))
      (node (ref "R2") (pin "2") (pinfunction "1_2") (pintype "passive"))
      (node (ref "R7") (pin "6") (pinfunction "2_6") (pintype "passive"))
    )
    (net (code "68") (name "Net-(IC1-AVDD)") (class "Default")
      (node (ref "C55") (pin "1") (pinfunction "1_1") (pintype "passive"))
      (node (ref "C56") (pin "+") (pinfunction "+_+") (pintype "passive"))
      (node (ref "C88") (pin "1") (pinfunction "1_1") (pintype "passive"))
      (node (ref "IC1") (pin "30") (pinfunction "AVDD_30") (pintype "input"))
      (node (ref "R92") (pin "2") (pinfunction "2_2") (pintype "passive"))
    )
    (net (code "69") (name "Net-(IC1-CLKI{slash}RC12{slash}OSC1)") (class "Default")
      (node (ref "C60") (pin "1") (pinfunction "1_1") (pintype "passive"))
      (node (ref "IC1") (pin "63") (pinfunction "CLKI/RC12/OSC1_63") (pintype "bidirectional"))
      (node (ref "X1") (pin "3") (pinfunction "2_3") (pintype "passive"))
    )
    (net (code "70") (name "Net-(IC1-CLKO{slash}RC15{slash}OSC2)") (class "Default")
      (node (ref "C61") (pin "1") (pinfunction "1_1") (pintype "passive"))
      (node (ref "IC1") (pin "64") (pinfunction "CLKO/RC15/OSC2_64") (pintype "bidirectional"))
      (node (ref "X1") (pin "1") (pinfunction "1_1") (pintype "passive"))
    )
    (net (code "71") (name "Net-(IC1-VCAP)") (class "Default")
      (node (ref "C53") (pin "1") (pinfunction "1_1") (pintype "passive"))
      (node (ref "C54") (pin "+") (pinfunction "+_+") (pintype "passive"))
      (node (ref "IC1") (pin "85") (pinfunction "VCAP_85") (pintype "input"))
    )
    (net (code "72") (name "Net-(IC2-EN_A)") (class "Default")
      (node (ref "C5") (pin "1") (pinfunction "1_1") (pintype "passive"))
      (node (ref "IC2") (pin "25") (pinfunction "EN_A_25") (pintype "input"))
      (node (ref "R11") (pin "4") (pinfunction "1_4") (pintype "passive"))
    )
    (net (code "73") (name "Net-(IC2-EN_B)") (class "Default")
      (node (ref "C43") (pin "1") (pinfunction "1_1") (pintype "passive"))
      (node (ref "IC2") (pin "16") (pinfunction "EN_B_16") (pintype "input"))
      (node (ref "R11") (pin "3") (pinfunction "1_3") (pintype "passive"))
    )
    (net (code "74") (name "Net-(IC2-RCA)") (class "Default")
      (node (ref "C7") (pin "1") (pinfunction "1_1") (pintype "passive"))
      (node (ref "IC2") (pin "30") (pinfunction "RCA_30") (pintype "input"))
      (node (ref "R11") (pin "2") (pinfunction "1_2") (pintype "passive"))
    )
    (net (code "75") (name "Net-(IC2-RCB)") (class "Default")
      (node (ref "C6") (pin "1") (pinfunction "1_1") (pintype "passive"))
      (node (ref "IC2") (pin "11") (pinfunction "RCB_11") (pintype "input"))
      (node (ref "R11") (pin "1") (pinfunction "1_1") (pintype "passive"))
    )
    (net (code "76") (name "Net-(IC2-SENSE_A)") (class "Default")
      (node (ref "IC2") (pin "29") (pinfunction "SENSE_A_29") (pintype "input"))
      (node (ref "R5") (pin "2") (pinfunction "2_2") (pintype "passive"))
    )
    (net (code "77") (name "Net-(IC2-SENSE_B)") (class "Default")
      (node (ref "IC2") (pin "12") (pinfunction "SENSE_B_12") (pintype "input"))
      (node (ref "R4") (pin "2") (pinfunction "2_2") (pintype "passive"))
    )
    (net (code "78") (name "Net-(IC2-VCP)") (class "Default")
      (node (ref "C2") (pin "2") (pinfunction "2_2") (pintype "passive"))
      (node (ref "IC2") (pin "24") (pinfunction "VCP_24") (pintype "input"))
    )
    (net (code "79") (name "Net-(IC2-VREF_A)") (class "Default")
      (node (ref "IC2") (pin "15") (pinfunction "VREF_B_15") (pintype "input"))
      (node (ref "IC2") (pin "26") (pinfunction "VREF_A_26") (pintype "input"))
      (node (ref "R3") (pin "2") (pinfunction "2_2") (pintype "passive"))
      (node (ref "R7") (pin "5") (pinfunction "2_5") (pintype "passive"))
    )
    (net (code "80") (name "Net-(IC6-HTH)") (class "Default")
      (node (ref "IC6") (pin "1") (pinfunction "HTH_1") (pintype "input"))
      (node (ref "R46") (pin "2") (pinfunction "2_2") (pintype "passive"))
      (node (ref "R47") (pin "1") (pinfunction "1_1") (pintype "passive"))
    )
    (net (code "81") (name "Net-(IC6-LTH)") (class "Default")
      (node (ref "IC6") (pin "3") (pinfunction "LTH_3") (pintype "input"))
      (node (ref "R33") (pin "1") (pinfunction "1_1") (pintype "passive"))
      (node (ref "R47") (pin "2") (pinfunction "2_2") (pintype "passive"))
    )
    (net (code "82") (name "Net-(IC6-VDD)") (class "Default")
      (node (ref "C35") (pin "1") (pinfunction "1_1") (pintype "passive"))
      (node (ref "IC6") (pin "5") (pinfunction "VDD_5") (pintype "input"))
      (node (ref "R28") (pin "1") (pinfunction "1_1") (pintype "passive"))
    )
    (net (code "83") (name "Net-(IC8-BOOST)") (class "Default")
      (node (ref "C25") (pin "2") (pinfunction "2_2") (pintype "passive"))
      (node (ref "IC8") (pin "2") (pinfunction "BOOST_2") (pintype "bidirectional"))
    )
    (net (code "84") (name "Net-(IC8-EN)") (class "Default")
      (node (ref "IC8") (pin "5") (pinfunction "EN_5") (pintype "bidirectional"))
      (node (ref "JP1") (pin "2") (pinfunction "2_2") (pintype "bidirectional"))
      (node (ref "R22") (pin "2") (pinfunction "2_2") (pintype "passive"))
    )
    (net (code "85") (name "Net-(IC8-FB)") (class "Default")
      (node (ref "C26") (pin "2") (pinfunction "2_2") (pintype "passive"))
      (node (ref "IC8") (pin "6") (pinfunction "FB_6") (pintype "bidirectional"))
      (node (ref "R19") (pin "1") (pinfunction "1_1") (pintype "passive"))
      (node (ref "R20") (pin "2") (pinfunction "2_2") (pintype "passive"))
    )
    (net (code "86") (name "Net-(IC8-RT)") (class "Default")
      (node (ref "IC8") (pin "8") (pinfunction "RT_8") (pintype "bidirectional"))
      (node (ref "R17") (pin "1") (pinfunction "1_1") (pintype "passive"))
    )
    (net (code "87") (name "Net-(IC8-SS)") (class "Default")
      (node (ref "IC8") (pin "7") (pinfunction "SS_7") (pintype "bidirectional"))
      (node (ref "R77") (pin "1") (pinfunction "1_1") (pintype "passive"))
    )
    (net (code "88") (name "Net-(IC8-SW)") (class "Default")
      (node (ref "C25") (pin "1") (pinfunction "1_1") (pintype "passive"))
      (node (ref "D7") (pin "K") (pinfunction "K_K") (pintype "passive"))
      (node (ref "IC8") (pin "3") (pinfunction "SW_3") (pintype "bidirectional"))
      (node (ref "L9") (pin "1") (pinfunction "1_1") (pintype "passive"))
    )
    (net (code "89") (name "Net-(IC10-OUT)") (class "Default")
      (node (ref "IC10") (pin "3") (pinfunction "OUT_3") (pintype "output"))
      (node (ref "R102") (pin "1") (pinfunction "1_1") (pintype "passive"))
    )
    (net (code "90") (name "Net-(IC10-VIN+)") (class "Default")
      (node (ref "C29") (pin "1") (pinfunction "1_1") (pintype "passive"))
      (node (ref "F1") (pin "1") (pinfunction "1_1") (pintype "passive"))
      (node (ref "IC10") (pin "5") (pinfunction "VIN+_5") (pintype "input"))
      (node (ref "R39") (pin "2") (pinfunction "2_2") (pintype "passive"))
    )
    (net (code "91") (name "Net-(IC11-WP)") (class "Default")
      (node (ref "IC11") (pin "7") (pinfunction "WP_7") (pintype "input"))
      (node (ref "R18") (pin "2") (pinfunction "2_2") (pintype "passive"))
      (node (ref "TP1") (pin "P$1") (pinfunction "TP_P$1") (pintype "passive"))
    )
    (net (code "92") (name "Net-(IC13-VIN)") (class "Default")
      (node (ref "C58") (pin "1") (pinfunction "1_1") (pintype "passive"))
      (node (ref "C59") (pin "1") (pinfunction "1_1") (pintype "passive"))
      (node (ref "IC13") (pin "1") (pinfunction "VIN_1") (pintype "bidirectional"))
      (node (ref "R93") (pin "2") (pinfunction "2_2") (pintype "passive"))
    )
    (net (code "93") (name "Net-(IC16A-+IN)") (class "Default")
      (node (ref "C62") (pin "1") (pinfunction "1_1") (pintype "passive"))
      (node (ref "IC16") (pin "3") (pinfunction "+IN_3") (pintype "input"))
      (node (ref "R95") (pin "2") (pinfunction "2_2") (pintype "passive"))
      (node (ref "R96") (pin "1") (pinfunction "1_1") (pintype "passive"))
    )
    (net (code "94") (name "Net-(IC16A--IN)") (class "Default")
      (node (ref "IC16") (pin "1") (pinfunction "OUT_1") (pintype "output"))
      (node (ref "IC16") (pin "2") (pinfunction "-IN_2") (pintype "input"))
      (node (ref "R101") (pin "2") (pinfunction "2_2") (pintype "passive"))
    )
    (net (code "95") (name "Net-(IC16B-+IN)") (class "Default")
      (node (ref "C63") (pin "1") (pinfunction "1_1") (pintype "passive"))
      (node (ref "IC16") (pin "5") (pinfunction "+IN_5") (pintype "input"))
      (node (ref "R98") (pin "2") (pinfunction "2_2") (pintype "passive"))
      (node (ref "R99") (pin "1") (pinfunction "1_1") (pintype "passive"))
    )
    (net (code "96") (name "Net-(IC16B--IN)") (class "Default")
      (node (ref "IC16") (pin "6") (pinfunction "-IN_6") (pintype "input"))
      (node (ref "IC16") (pin "7") (pinfunction "OUT_7") (pintype "output"))
      (node (ref "R100") (pin "2") (pinfunction "2_2") (pintype "passive"))
    )
    (net (code "97") (name "Net-(IC16C-V+)") (class "Default")
      (node (ref "C67") (pin "1") (pinfunction "1_1") (pintype "passive"))
      (node (ref "IC16") (pin "8") (pinfunction "V+_8") (pintype "input"))
      (node (ref "R103") (pin "1") (pinfunction "1_1") (pintype "passive"))
    )
    (net (code "98") (name "Net-(J12-+5V)") (class "Default")
      (node (ref "C85") (pin "1") (pinfunction "1_1") (pintype "passive"))
      (node (ref "D6") (pin "A") (pinfunction "A_A") (pintype "passive"))
      (node (ref "IC15") (pin "4") (pinfunction "4_4") (pintype "input"))
      (node (ref "J12") (pin "1_+5V") (pinfunction "+5V_1_+5V") (pintype "bidirectional"))
      (node (ref "R128") (pin "1") (pinfunction "1_1") (pintype "passive"))
    )
    (net (code "99") (name "Net-(JP1-Pad1)") (class "Default")
      (node (ref "JP1") (pin "1") (pinfunction "1_1") (pintype "bidirectional"))
      (node (ref "R21") (pin "1") (pinfunction "1_1") (pintype "passive"))
    )
    (net (code "100") (name "Net-(L13-Pad2)") (class "Default")
      (node (ref "L13") (pin "2") (pinfunction "2_2") (pintype "passive"))
      (node (ref "R92") (pin "1") (pinfunction "1_1") (pintype "passive"))
    )
    (net (code "101") (name "Net-(Q1B-G)") (class "Default")
      (node (ref "C70") (pin "2") (pinfunction "2_2") (pintype "passive"))
      (node (ref "Q1") (pin "5") (pinfunction "G_5") (pintype "passive"))
      (node (ref "R75") (pin "1") (pinfunction "1_1") (pintype "passive"))
      (node (ref "R82") (pin "2") (pinfunction "2_2") (pintype "passive"))
    )
    (net (code "102") (name "Net-(Q1B-S)") (class "Default")
      (node (ref "Q1") (pin "4") (pinfunction "S_4") (pintype "passive"))
      (node (ref "R106") (pin "1") (pinfunction "1_1") (pintype "passive"))
    )
    (net (code "103") (name "Net-(Q2B-G)") (class "Default")
      (node (ref "C69") (pin "2") (pinfunction "2_2") (pintype "passive"))
      (node (ref "Q2") (pin "5") (pinfunction "G_5") (pintype "passive"))
      (node (ref "R24") (pin "1") (pinfunction "1_1") (pintype "passive"))
      (node (ref "R65") (pin "2") (pinfunction "2_2") (pintype "passive"))
    )
    (net (code "104") (name "Net-(Q2B-S)") (class "Default")
      (node (ref "Q2") (pin "4") (pinfunction "S_4") (pintype "passive"))
      (node (ref "R105") (pin "1") (pinfunction "1_1") (pintype "passive"))
    )
    (net (code "105") (name "Net-(Q3-Q2D1)") (class "Default")
      (node (ref "Q3") (pin "2") (pinfunction "Q2D1_2") (pintype "bidirectional"))
      (node (ref "Q3") (pin "3") (pinfunction "Q2D2_3") (pintype "bidirectional"))
      (node (ref "R6") (pin "1") (pinfunction "1_1") (pintype "passive"))
      (node (ref "R8") (pin "1") (pinfunction "1_1") (pintype "passive"))
    )
    (net (code "106") (name "Net-(Q3-Q2G)") (class "Default")
      (node (ref "Q3") (pin "6") (pinfunction "Q2G_6") (pintype "input"))
      (node (ref "R9") (pin "3") (pinfunction "1_3") (pintype "passive"))
    )
    (net (code "107") (name "Net-(Q4A-D)") (class "Default")
      (node (ref "C33") (pin "2") (pinfunction "2_2") (pintype "passive"))
      (node (ref "Q4") (pin "6") (pinfunction "D_6") (pintype "passive"))
      (node (ref "Q5") (pin "1") (pinfunction "G_1") (pintype "passive"))
      (node (ref "R42") (pin "2") (pinfunction "2_2") (pintype "passive"))
    )
    (net (code "108") (name "Net-(Q4A-S)") (class "Default")
      (node (ref "Q4") (pin "1") (pinfunction "S_1") (pintype "passive"))
      (node (ref "R40") (pin "2") (pinfunction "2_2") (pintype "passive"))
    )
    (net (code "109") (name "Net-(Q4B-D)") (class "Default")
      (node (ref "C34") (pin "2") (pinfunction "2_2") (pintype "passive"))
      (node (ref "Q4") (pin "3") (pinfunction "D_3") (pintype "passive"))
      (node (ref "Q5") (pin "3") (pinfunction "G_3") (pintype "passive"))
      (node (ref "R45") (pin "2") (pinfunction "2_2") (pintype "passive"))
    )
    (net (code "110") (name "Net-(Q4B-S)") (class "Default")
      (node (ref "Q4") (pin "4") (pinfunction "S_4") (pintype "passive"))
      (node (ref "R43") (pin "2") (pinfunction "2_2") (pintype "passive"))
    )
    (net (code "111") (name "Net-(Q5A-D)") (class "Default")
      (node (ref "F1") (pin "2") (pinfunction "2_2") (pintype "passive"))
      (node (ref "Q5") (pin "6") (pinfunction "D_6") (pintype "passive"))
      (node (ref "R35") (pin "1") (pinfunction "1_1") (pintype "passive"))
      (node (ref "R37") (pin "1") (pinfunction "1_1") (pintype "passive"))
      (node (ref "R97") (pin "1") (pinfunction "1_1") (pintype "passive"))
    )
    (net (code "112") (name "Net-(R23-Pad1)") (class "Default")
      (node (ref "R23") (pin "1") (pinfunction "1_1") (pintype "passive"))
      (node (ref "R49") (pin "2") (pinfunction "2_2") (pintype "passive"))
    )
    (net (code "113") (name "Net-(R35-Pad2)") (class "Default")
      (node (ref "R35") (pin "2") (pinfunction "2_2") (pintype "passive"))
      (node (ref "R36") (pin "1") (pinfunction "1_1") (pintype "passive"))
      (node (ref "R37") (pin "2") (pinfunction "2_2") (pintype "passive"))
      (node (ref "R38") (pin "1") (pinfunction "1_1") (pintype "passive"))
    )
    (net (code "114") (name "Net-(R94-Pad2)") (class "Default")
      (node (ref "R94") (pin "2") (pinfunction "2_2") (pintype "passive"))
      (node (ref "R95") (pin "1") (pinfunction "1_1") (pintype "passive"))
    )
    (net (code "115") (name "Net-(R97-Pad2)") (class "Default")
      (node (ref "R97") (pin "2") (pinfunction "2_2") (pintype "passive"))
      (node (ref "R98") (pin "1") (pinfunction "1_1") (pintype "passive"))
    )
    (net (code "116") (name "PGND") (class "Default")
      (node (ref "C1") (pin "2") (pinfunction "2_2") (pintype "passive"))
      (node (ref "C12") (pin "2") (pinfunction "2_2") (pintype "passive"))
      (node (ref "C3") (pin "2") (pinfunction "2_2") (pintype "passive"))
      (node (ref "C38") (pin "2") (pinfunction "2_2") (pintype "passive"))
      (node (ref "C4") (pin "2") (pinfunction "2_2") (pintype "passive"))
      (node (ref "C43") (pin "2") (pinfunction "2_2") (pintype "passive"))
      (node (ref "C44") (pin "2") (pinfunction "2_2") (pintype "passive"))
      (node (ref "C5") (pin "2") (pinfunction "2_2") (pintype "passive"))
      (node (ref "C6") (pin "2") (pinfunction "2_2") (pintype "passive"))
      (node (ref "C7") (pin "2") (pinfunction "2_2") (pintype "passive"))
      (node (ref "D8") (pin "A") (pinfunction "A_A") (pintype "passive"))
      (node (ref "D9") (pin "1") (pinfunction "A_1") (pintype "passive"))
      (node (ref "IC2") (pin "1") (pinfunction "GND1_1") (pintype "input"))
      (node (ref "IC2") (pin "2") (pinfunction "GND2_2") (pintype "input"))
      (node (ref "IC2") (pin "21") (pinfunction "GND21_21") (pintype "input"))
      (node (ref "IC2") (pin "3") (pinfunction "GND3_3") (pintype "input"))
      (node (ref "IC2") (pin "4") (pinfunction "GND4_4") (pintype "input"))
      (node (ref "IC2") (pin "5") (pinfunction "GND5_5") (pintype "input"))
      (node (ref "IC2") (pin "6") (pinfunction "GND6_6") (pintype "input"))
      (node (ref "IC2") (pin "7") (pinfunction "GND7_7") (pintype "input"))
      (node (ref "IC2") (pin "8") (pinfunction "GND8_8") (pintype "input"))
      (node (ref "IC2") (pin "G") (pinfunction "GNEXP_G") (pintype "input"))
      (node (ref "J14") (pin "5") (pinfunction "5_5") (pintype "passive"))
      (node (ref "J15") (pin "5") (pinfunction "5_5") (pintype "passive"))
      (node (ref "L2") (pin "1") (pinfunction "1_1") (pintype "passive"))
      (node (ref "Q3") (pin "1") (pinfunction "Q1S_1") (pintype "bidirectional"))
      (node (ref "R1") (pin "2") (pinfunction "1_2") (pintype "passive"))
      (node (ref "R1") (pin "4") (pinfunction "1_4") (pintype "passive"))
      (node (ref "R10") (pin "1") (pinfunction "1_1") (pintype "passive"))
      (node (ref "R10") (pin "2") (pinfunction "1_2") (pintype "passive"))
      (node (ref "R10") (pin "3") (pinfunction "1_3") (pintype "passive"))
      (node (ref "R10") (pin "4") (pinfunction "1_4") (pintype "passive"))
      (node (ref "R11") (pin "7") (pinfunction "2_7") (pintype "passive"))
      (node (ref "R11") (pin "8") (pinfunction "2_8") (pintype "passive"))
      (node (ref "R3") (pin "1") (pinfunction "1_1") (pintype "passive"))
      (node (ref "R4") (pin "1") (pinfunction "1_1") (pintype "passive"))
      (node (ref "R5") (pin "1") (pinfunction "1_1") (pintype "passive"))
      (node (ref "R50") (pin "5") (pinfunction "2_5") (pintype "passive"))
      (node (ref "R50") (pin "6") (pinfunction "2_6") (pintype "passive"))
      (node (ref "R9") (pin "2") (pinfunction "1_2") (pintype "passive"))
    )
    (net (code "117") (name "VACT") (class "Default")
      (node (ref "C1") (pin "1") (pinfunction "1_1") (pintype "passive"))
      (node (ref "C37") (pin "1") (pinfunction "1_1") (pintype "passive"))
      (node (ref "C38") (pin "1") (pinfunction "1_1") (pintype "passive"))
      (node (ref "D1") (pin "1") (pinfunction "A_1") (pintype "passive"))
      (node (ref "D8") (pin "C") (pinfunction "C_C") (pintype "passive"))
      (node (ref "IC2") (pin "20") (pinfunction "VS_B_20") (pintype "input"))
      (node (ref "IC2") (pin "22") (pinfunction "VS_A_22") (pintype "input"))
      (node (ref "R7") (pin "3") (pinfunction "1_3") (pintype "passive"))
    )
    (net (code "118") (name "VBAT") (class "Default")
      (node (ref "C22") (pin "1") (pinfunction "1_1") (pintype "passive"))
      (node (ref "C23") (pin "1") (pinfunction "1_1") (pintype "passive"))
      (node (ref "C83") (pin "1") (pinfunction "1_1") (pintype "passive"))
      (node (ref "C84") (pin "1") (pinfunction "1_1") (pintype "passive"))
      (node (ref "IC10") (pin "4") (pinfunction "VIN-_4") (pintype "input"))
      (node (ref "IC8") (pin "4") (pinfunction "VIN_4") (pintype "bidirectional"))
      (node (ref "JP1") (pin "3") (pinfunction "3_3") (pintype "bidirectional"))
      (node (ref "Q3") (pin "4") (pinfunction "Q2S_4") (pintype "bidirectional"))
      (node (ref "R22") (pin "1") (pinfunction "1_1") (pintype "passive"))
      (node (ref "R33") (pin "2") (pinfunction "2_2") (pintype "passive"))
      (node (ref "R39") (pin "1") (pinfunction "1_1") (pintype "passive"))
      (node (ref "R9") (pin "6") (pinfunction "2_6") (pintype "passive"))
    )
    (net (code "119") (name "unconnected-(IC1-AN8{slash}RPB8{slash}CTED10{slash}RB8-Pad32)") (class "Default")
      (node (ref "IC1") (pin "32") (pinfunction "AN8/RPB8/CTED10/RB8_32") (pintype "bidirectional"))
    )
    (net (code "120") (name "unconnected-(IC1-AN9{slash}RPB9{slash}CTED4{slash}RB9-Pad33)") (class "Default")
      (node (ref "IC1") (pin "33") (pinfunction "AN9/RPB9/CTED4/RB9_33") (pintype "bidirectional"))
    )
    (net (code "121") (name "unconnected-(IC1-AN11{slash}PMA12{slash}RB11-Pad35)") (class "Default")
      (node (ref "IC1") (pin "35") (pinfunction "AN11/PMA12/RB11_35") (pintype "bidirectional"))
    )
    (net (code "122") (name "unconnected-(IC1-AN12{slash}PMA11{slash}RB12-Pad41)") (class "Default")
      (node (ref "IC1") (pin "41") (pinfunction "AN12/PMA11/RB12_41") (pintype "bidirectional"))
    )
    (net (code "123") (name "unconnected-(IC1-AN13{slash}RB13-Pad42)") (class "Default")
      (node (ref "IC1") (pin "42") (pinfunction "AN13/RB13_42") (pintype "bidirectional"))
    )
    (net (code "124") (name "unconnected-(IC1-AN14{slash}RPB14{slash}PMA1{slash}CTED5{slash}RB14-Pad43)") (class "Default")
      (node (ref "IC1") (pin "43") (pinfunction "AN14/RPB14/PMA1/CTED5/RB14_43") (pintype "bidirectional"))
    )
    (net (code "125") (name "unconnected-(IC1-AN15{slash}RPB15{slash}PMA0{slash}CTED6{slash}{slash}RB15-Pad44)") (class "Default")
      (node (ref "IC1") (pin "44") (pinfunction "AN15/RPB15/PMA0/CTED6//RB15_44") (pintype "bidirectional"))
    )
    (net (code "126") (name "unconnected-(IC1-AN20{slash}PMD2{slash}RE2-Pad98)") (class "Default")
      (node (ref "IC1") (pin "98") (pinfunction "AN20/PMD2/RE2_98") (pintype "bidirectional"))
    )
    (net (code "127") (name "unconnected-(IC1-AN21{slash}PMD4{slash}RE4-Pad100)") (class "Default")
      (node (ref "IC1") (pin "100") (pinfunction "AN21/PMD4/RE4_100") (pintype "bidirectional"))
    )
    (net (code "128") (name "unconnected-(IC1-AN22{slash}RPE5{slash}PMD5{slash}RE5-Pad3)") (class "Default")
      (node (ref "IC1") (pin "3") (pinfunction "AN22/RPE5/PMD5/RE5_3") (pintype "bidirectional"))
    )
    (net (code "129") (name "unconnected-(IC1-AN23{slash}PMD6{slash}RE6-Pad4)") (class "Default")
      (node (ref "IC1") (pin "4") (pinfunction "AN23/PMD6/RE6_4") (pintype "bidirectional"))
    )
    (net (code "130") (name "unconnected-(IC1-AN24{slash}RPD1{slash}RD1-Pad76)") (class "Default")
      (node (ref "IC1") (pin "76") (pinfunction "AN24/RPD1/RD1_76") (pintype "bidirectional"))
    )
    (net (code "131") (name "unconnected-(IC1-AN25{slash}RPD2{slash}RD2-Pad77)") (class "Default")
      (node (ref "IC1") (pin "77") (pinfunction "AN25/RPD2/RD2_77") (pintype "bidirectional"))
    )
    (net (code "132") (name "unconnected-(IC1-AN26{slash}RPD3{slash}RD3-Pad78)") (class "Default")
      (node (ref "IC1") (pin "78") (pinfunction "AN26/RPD3/RD3_78") (pintype "bidirectional"))
    )
    (net (code "133") (name "unconnected-(IC1-AN27{slash}PMD7{slash}RE7-Pad5)") (class "Default")
      (node (ref "IC1") (pin "5") (pinfunction "AN27/PMD7/RE7_5") (pintype "bidirectional"))
    )
    (net (code "134") (name "unconnected-(IC1-CVREFOUT{slash}AN10{slash}RPB10{slash}PMA13{slash}CTED11{slash}RB10-Pad34)") (class "Default")
      (node (ref "IC1") (pin "34") (pinfunction "CVREFOUT/AN10/RPB10/PMA13/CTED11/RB10_34") (pintype "bidirectional"))
    )
    (net (code "135") (name "unconnected-(IC1-PGEC3{slash}AN2{slash}C2INB{slash}RPB2{slash}CTED13{slash}RB2-Pad23)") (class "Default")
      (node (ref "IC1") (pin "23") (pinfunction "PGEC3/AN2/C2INB/RPB2/CTED13/RB2_23") (pintype "bidirectional"))
    )
    (net (code "136") (name "unconnected-(IC1-PMD0{slash}RE0-Pad93)") (class "Default")
      (node (ref "IC1") (pin "93") (pinfunction "PMD0/RE0_93") (pintype "bidirectional"))
    )
    (net (code "137") (name "unconnected-(IC1-PMD1{slash}RE1-Pad94)") (class "Default")
      (node (ref "IC1") (pin "94") (pinfunction "PMD1/RE1_94") (pintype "bidirectional"))
    )
    (net (code "138") (name "unconnected-(IC1-PMD13{slash}RD13-Pad80)") (class "Default")
      (node (ref "IC1") (pin "80") (pinfunction "PMD13/RD13_80") (pintype "bidirectional"))
    )
    (net (code "139") (name "unconnected-(IC1-PMD14{slash}RD6-Pad83)") (class "Default")
      (node (ref "IC1") (pin "83") (pinfunction "PMD14/RD6_83") (pintype "bidirectional"))
    )
    (net (code "140") (name "unconnected-(IC1-RPC1{slash}RC1-Pad6)") (class "Default")
      (node (ref "IC1") (pin "6") (pinfunction "RPC1/RC1_6") (pintype "bidirectional"))
    )
    (net (code "141") (name "unconnected-(IC1-RPC2{slash}RC2-Pad7)") (class "Default")
      (node (ref "IC1") (pin "7") (pinfunction "RPC2/RC2_7") (pintype "bidirectional"))
    )
    (net (code "142") (name "unconnected-(IC1-RPC3{slash}RC3-Pad8)") (class "Default")
      (node (ref "IC1") (pin "8") (pinfunction "RPC3/RC3_8") (pintype "bidirectional"))
    )
    (net (code "143") (name "unconnected-(IC1-RPD0{slash}INT0{slash}RD0-Pad72)") (class "Default")
      (node (ref "IC1") (pin "72") (pinfunction "RPD0/INT0/RD0_72") (pintype "bidirectional"))
    )
    (net (code "144") (name "unconnected-(IC1-RPD4{slash}PMWR{slash}RD4-Pad81)") (class "Default")
      (node (ref "IC1") (pin "81") (pinfunction "RPD4/PMWR/RD4_81") (pintype "bidirectional"))
    )
    (net (code "145") (name "unconnected-(IC1-RPD5{slash}PMRD{slash}RD5-Pad82)") (class "Default")
      (node (ref "IC1") (pin "82") (pinfunction "RPD5/PMRD/RD5_82") (pintype "bidirectional"))
    )
    (net (code "146") (name "unconnected-(IC1-RPD8{slash}RTCC{slash}RD8-Pad68)") (class "Default")
      (node (ref "IC1") (pin "68") (pinfunction "RPD8/RTCC/RD8_68") (pintype "bidirectional"))
    )
    (net (code "147") (name "unconnected-(IC1-RPD9{slash}RD9-Pad69)") (class "Default")
      (node (ref "IC1") (pin "69") (pinfunction "RPD9/RD9_69") (pintype "bidirectional"))
    )
    (net (code "148") (name "unconnected-(IC1-RPD10{slash}SCK1{slash}PMCS2{slash}RD10-Pad70)") (class "Default")
      (node (ref "IC1") (pin "70") (pinfunction "RPD10/SCK1/PMCS2/RD10_70") (pintype "bidirectional"))
    )
    (net (code "149") (name "unconnected-(IC1-RPD11{slash}PMCS1{slash}RD11-Pad71)") (class "Default")
      (node (ref "IC1") (pin "71") (pinfunction "RPD11/PMCS1/RD11_71") (pintype "bidirectional"))
    )
    (net (code "150") (name "unconnected-(IC1-RPD12{slash}PMD12{slash}RD12-Pad79)") (class "Default")
      (node (ref "IC1") (pin "79") (pinfunction "RPD12/PMD12/RD12_79") (pintype "bidirectional"))
    )
    (net (code "151") (name "unconnected-(IC1-RPD14{slash}RD14-Pad47)") (class "Default")
      (node (ref "IC1") (pin "47") (pinfunction "RPD14/RD14_47") (pintype "bidirectional"))
    )
    (net (code "152") (name "unconnected-(IC1-RPD15{slash}RD15-Pad48)") (class "Default")
      (node (ref "IC1") (pin "48") (pinfunction "RPD15/RD15_48") (pintype "bidirectional"))
    )
    (net (code "153") (name "unconnected-(IC1-RPE3{slash}PMD3{slash}RE3-Pad99)") (class "Default")
      (node (ref "IC1") (pin "99") (pinfunction "RPE3/PMD3/RE3_99") (pintype "bidirectional"))
    )
    (net (code "154") (name "unconnected-(IC1-RPE8{slash}RE8-Pad18)") (class "Default")
      (node (ref "IC1") (pin "18") (pinfunction "RPE8/RE8_18") (pintype "bidirectional"))
    )
    (net (code "155") (name "unconnected-(IC1-RPE9{slash}RE9-Pad19)") (class "Default")
      (node (ref "IC1") (pin "19") (pinfunction "RPE9/RE9_19") (pintype "bidirectional"))
    )
    (net (code "156") (name "unconnected-(IC1-RPF3{slash}USBID{slash}RF3-Pad51)") (class "Default")
      (node (ref "IC1") (pin "51") (pinfunction "RPF3/USBID/RF3_51") (pintype "bidirectional"))
    )
    (net (code "157") (name "unconnected-(IC1-RPF4{slash}PMA9{slash}RF4-Pad49)") (class "Default")
      (node (ref "IC1") (pin "49") (pinfunction "RPF4/PMA9/RF4_49") (pintype "bidirectional"))
    )
    (net (code "158") (name "unconnected-(IC1-RPF5{slash}PMA8{slash}RF5-Pad50)") (class "Default")
      (node (ref "IC1") (pin "50") (pinfunction "RPF5/PMA8/RF5_50") (pintype "bidirectional"))
    )
    (net (code "159") (name "unconnected-(IC1-RPF12{slash}RF12-Pad40)") (class "Default")
      (node (ref "IC1") (pin "40") (pinfunction "RPF12/RF12_40") (pintype "bidirectional"))
    )
    (net (code "160") (name "unconnected-(IC1-RPF13{slash}RF13-Pad39)") (class "Default")
      (node (ref "IC1") (pin "39") (pinfunction "RPF13/RF13_39") (pintype "bidirectional"))
    )
    (net (code "161") (name "unconnected-(IC1-RPG0{slash}PMD8{slash}RG0-Pad90)") (class "Default")
      (node (ref "IC1") (pin "90") (pinfunction "RPG0/PMD8/RG0_90") (pintype "bidirectional"))
    )
    (net (code "162") (name "unconnected-(IC1-RPG1{slash}PMD9{slash}RG1-Pad89)") (class "Default")
      (node (ref "IC1") (pin "89") (pinfunction "RPG1/PMD9/RG1_89") (pintype "bidirectional"))
    )
    (net (code "163") (name "unconnected-(IC1-SCL2{slash}RA2-Pad58)") (class "Default")
      (node (ref "IC1") (pin "58") (pinfunction "SCL2/RA2_58") (pintype "bidirectional"))
    )
    (net (code "164") (name "unconnected-(IC1-SDA2{slash}RA3-Pad59)") (class "Default")
      (node (ref "IC1") (pin "59") (pinfunction "SDA2/RA3_59") (pintype "bidirectional"))
    )
    (net (code "165") (name "unconnected-(IC1-SOSCI{slash}RPC13{slash}RC13-Pad73)") (class "Default")
      (node (ref "IC1") (pin "73") (pinfunction "SOSCI/RPC13/RC13_73") (pintype "bidirectional"))
    )
    (net (code "166") (name "unconnected-(IC1-SOSCO{slash}RPC14{slash}T1CK{slash}RC14-Pad74)") (class "Default")
      (node (ref "IC1") (pin "74") (pinfunction "SOSCO/RPC14/T1CK/RC14_74") (pintype "bidirectional"))
    )
    (net (code "167") (name "unconnected-(IC1-TCK{slash}CTED2{slash}RA1-Pad38)") (class "Default")
      (node (ref "IC1") (pin "38") (pinfunction "TCK/CTED2/RA1_38") (pintype "bidirectional"))
    )
    (net (code "168") (name "unconnected-(IC1-TDI{slash}CTED9{slash}RA4-Pad60)") (class "Default")
      (node (ref "IC1") (pin "60") (pinfunction "TDI/CTED9/RA4_60") (pintype "bidirectional"))
    )
    (net (code "169") (name "unconnected-(IC1-TDO{slash}RA5-Pad61)") (class "Default")
      (node (ref "IC1") (pin "61") (pinfunction "TDO/RA5_61") (pintype "bidirectional"))
    )
    (net (code "170") (name "unconnected-(IC1-TMS{slash}CTED1{slash}RA0-Pad17)") (class "Default")
      (node (ref "IC1") (pin "17") (pinfunction "TMS/CTED1/RA0_17") (pintype "bidirectional"))
    )
    (net (code "171") (name "unconnected-(IC1-TRCLK{slash}RA6-Pad91)") (class "Default")
      (node (ref "IC1") (pin "91") (pinfunction "TRCLK/RA6_91") (pintype "bidirectional"))
    )
    (net (code "172") (name "unconnected-(IC1-TRD0{slash}RG13-Pad97)") (class "Default")
      (node (ref "IC1") (pin "97") (pinfunction "TRD0/RG13_97") (pintype "bidirectional"))
    )
    (net (code "173") (name "unconnected-(IC1-TRD2{slash}RG14-Pad95)") (class "Default")
      (node (ref "IC1") (pin "95") (pinfunction "TRD2/RG14_95") (pintype "bidirectional"))
    )
    (net (code "174") (name "unconnected-(IC1-TRD3{slash}CTED8{slash}RA7-Pad92)") (class "Default")
      (node (ref "IC1") (pin "92") (pinfunction "TRD3/CTED8/RA7_92") (pintype "bidirectional"))
    )
    (net (code "175") (name "unconnected-(IC8-PG-Pad9)") (class "Default")
      (node (ref "IC8") (pin "9") (pinfunction "PG_9") (pintype "bidirectional"))
    )
    (net (code "176") (name "unconnected-(Q1A-D-Pad6)") (class "Default")
      (node (ref "Q1") (pin "6") (pinfunction "D_6") (pintype "passive"))
    )
    (net (code "177") (name "unconnected-(Q1A-D1-PadP1)") (class "Default")
      (node (ref "Q1") (pin "P1") (pinfunction "D1_P1") (pintype "passive"))
    )
    (net (code "178") (name "unconnected-(Q1A-G-Pad2)") (class "Default")
      (node (ref "Q1") (pin "2") (pinfunction "G_2") (pintype "passive"))
    )
    (net (code "179") (name "unconnected-(Q1A-S-Pad1)") (class "Default")
      (node (ref "Q1") (pin "1") (pinfunction "S_1") (pintype "passive"))
    )
    (net (code "180") (name "unconnected-(Q2A-D-Pad6)") (class "Default")
      (node (ref "Q2") (pin "6") (pinfunction "D_6") (pintype "passive"))
    )
    (net (code "181") (name "unconnected-(Q2A-D1-PadP1)") (class "Default")
      (node (ref "Q2") (pin "P1") (pinfunction "D1_P1") (pintype "passive"))
    )
    (net (code "182") (name "unconnected-(Q2A-G-Pad2)") (class "Default")
      (node (ref "Q2") (pin "2") (pinfunction "G_2") (pintype "passive"))
    )
    (net (code "183") (name "unconnected-(Q2A-S-Pad1)") (class "Default")
      (node (ref "Q2") (pin "1") (pinfunction "S_1") (pintype "passive"))
    )
  )
)
